# in3watch.net
KiCad netlist of a schematic drawn in EAGLE
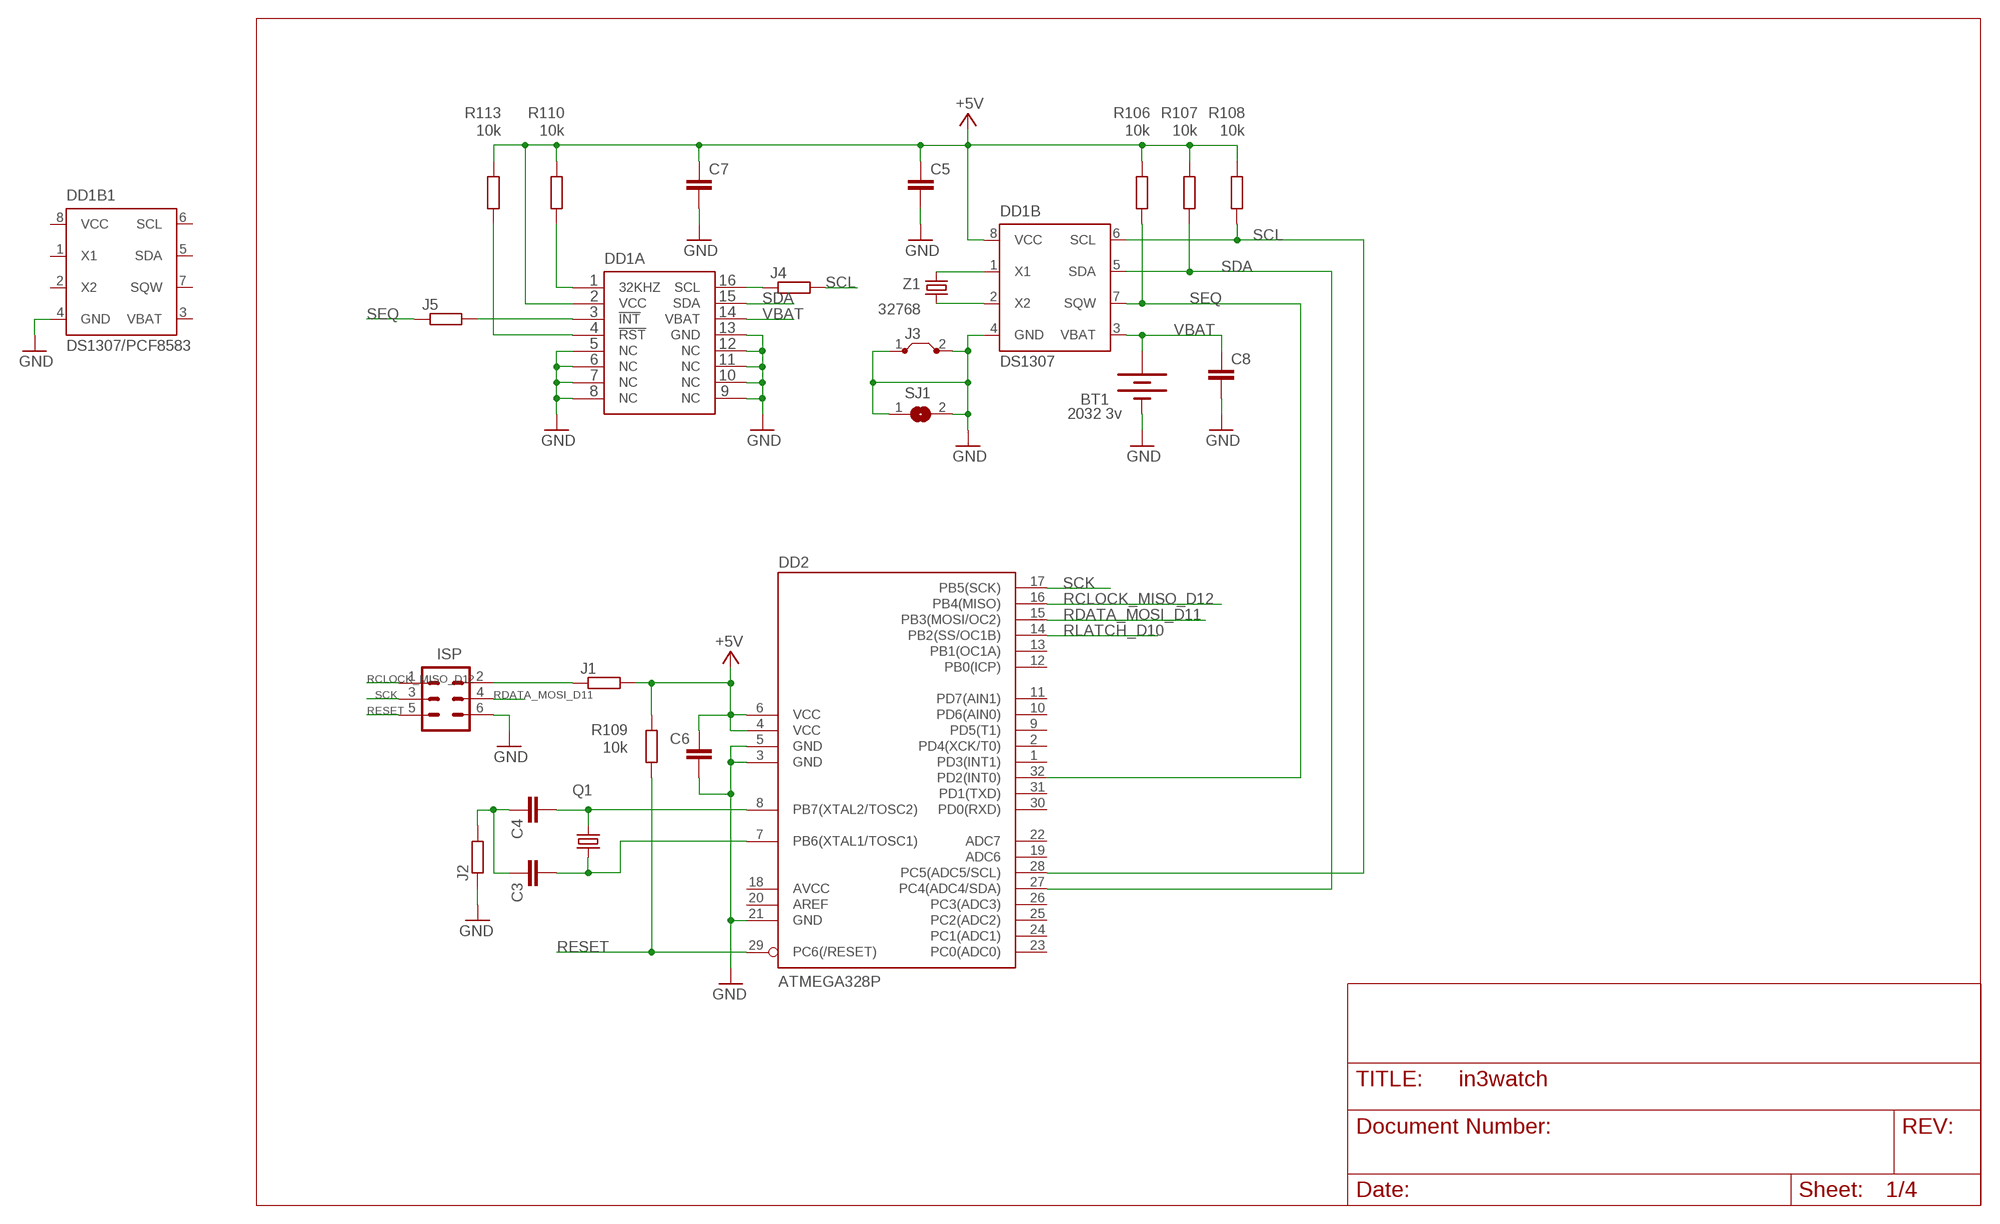
[diagram p0: schematic, sheet 1]
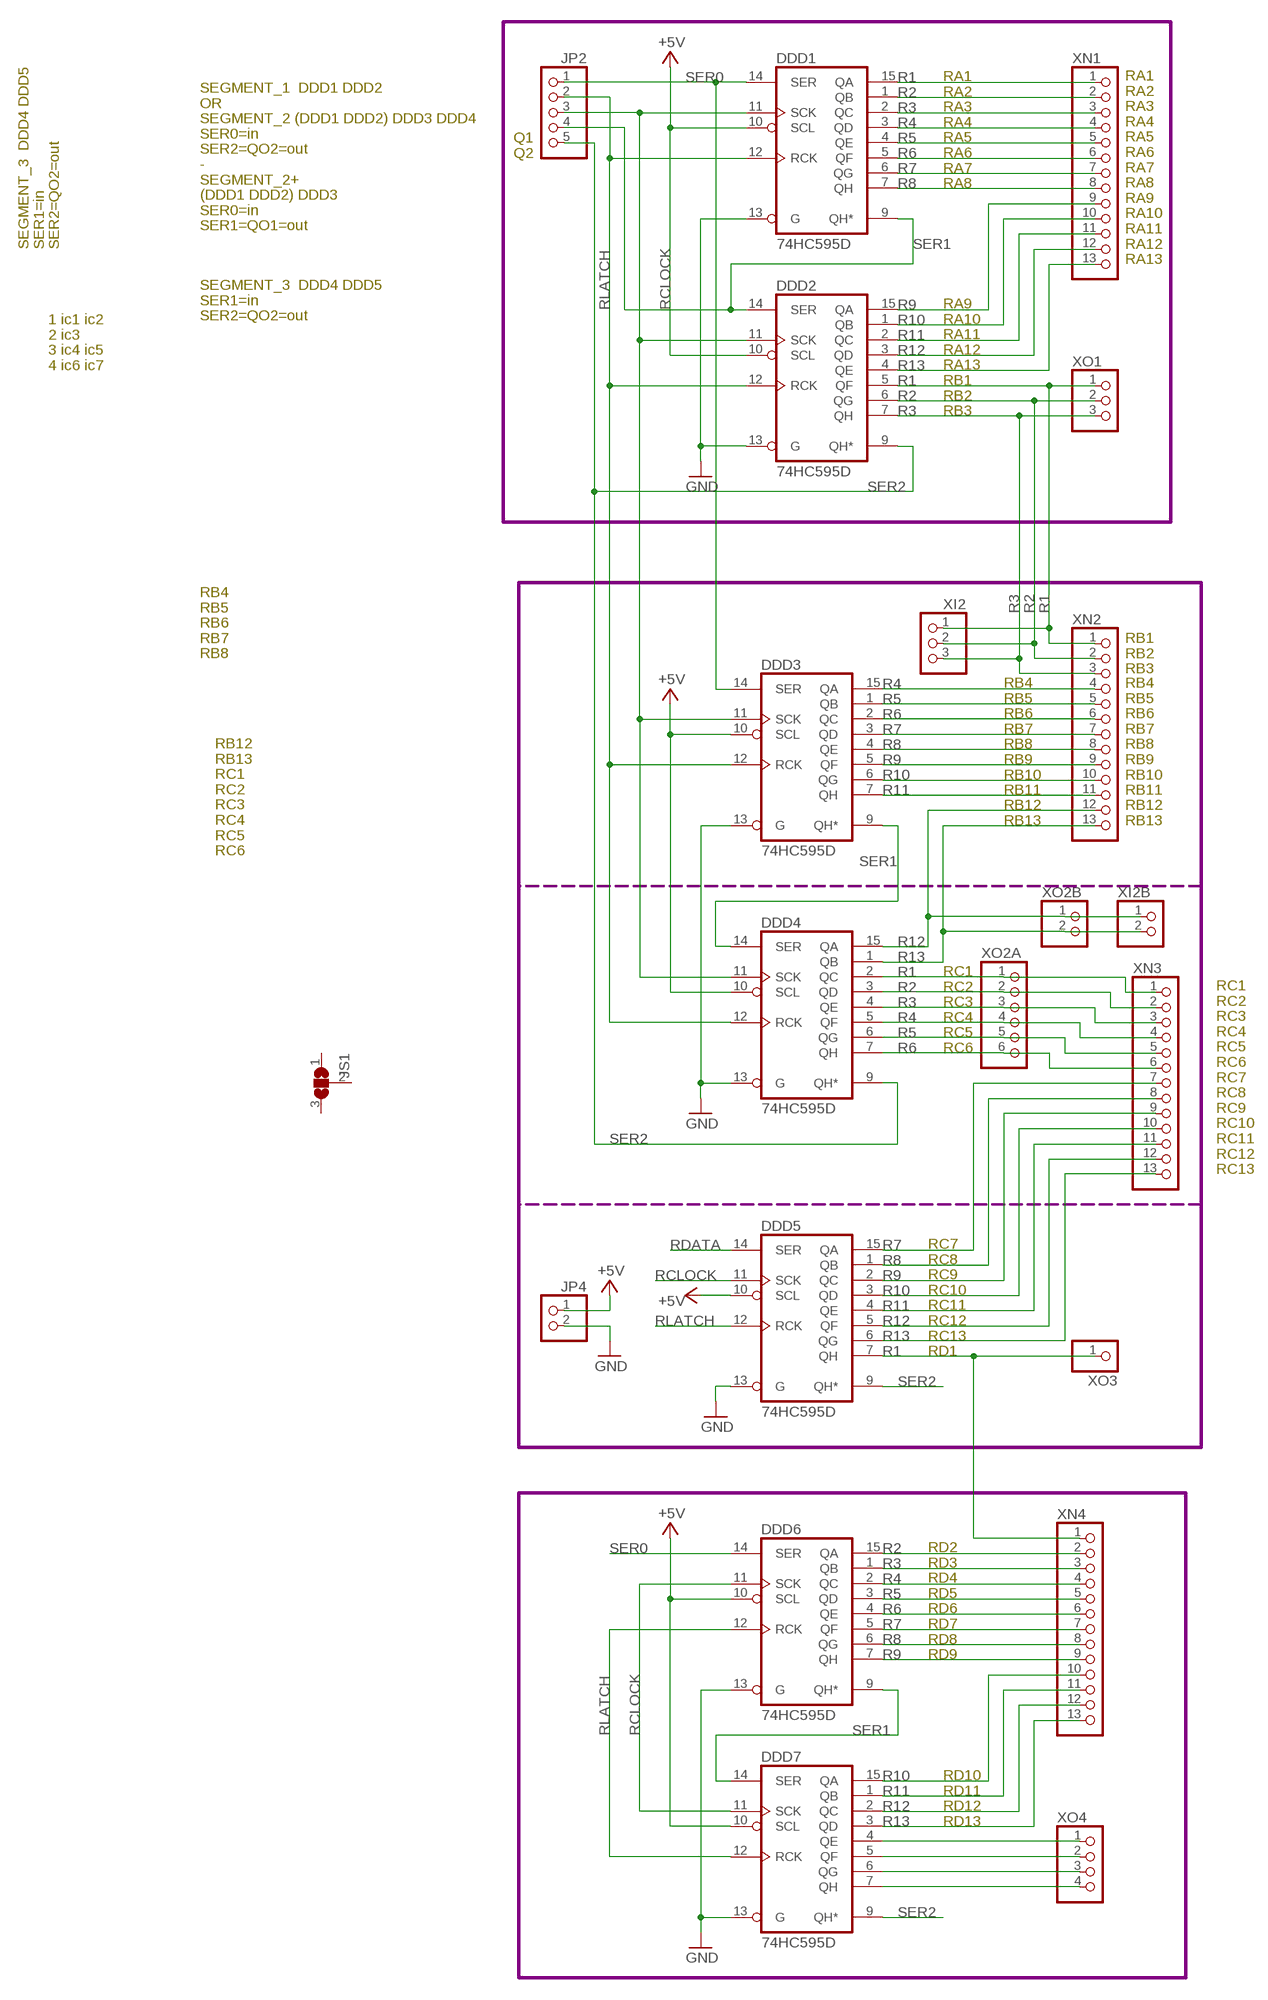
[diagram p1: schematic, sheet 2, part 1 of 2]
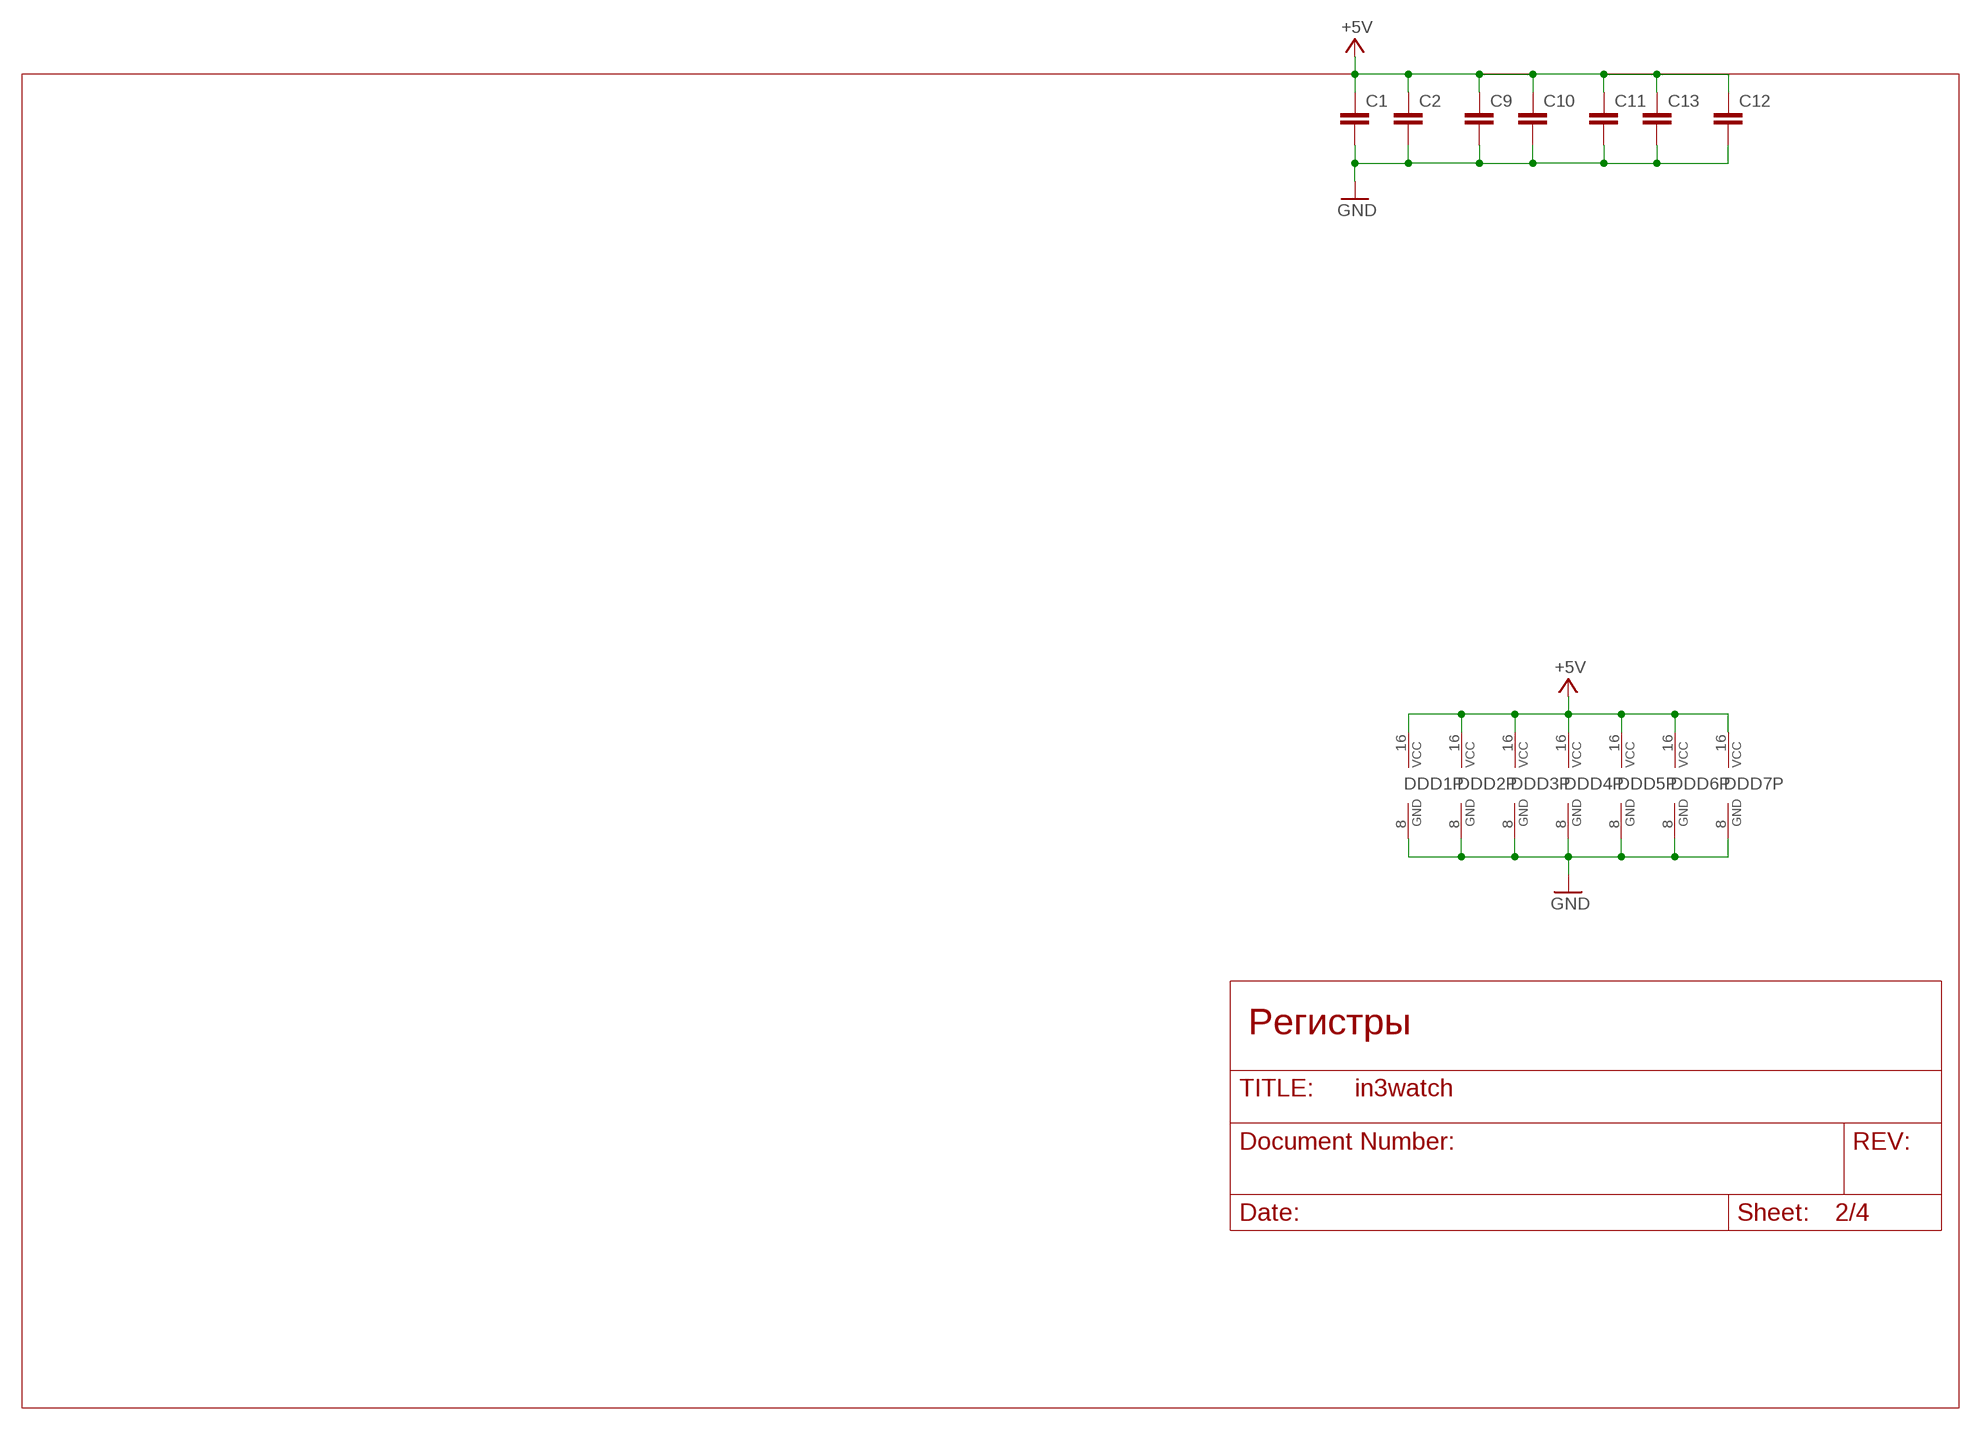
[diagram p2: schematic, sheet 2, part 2 of 2]
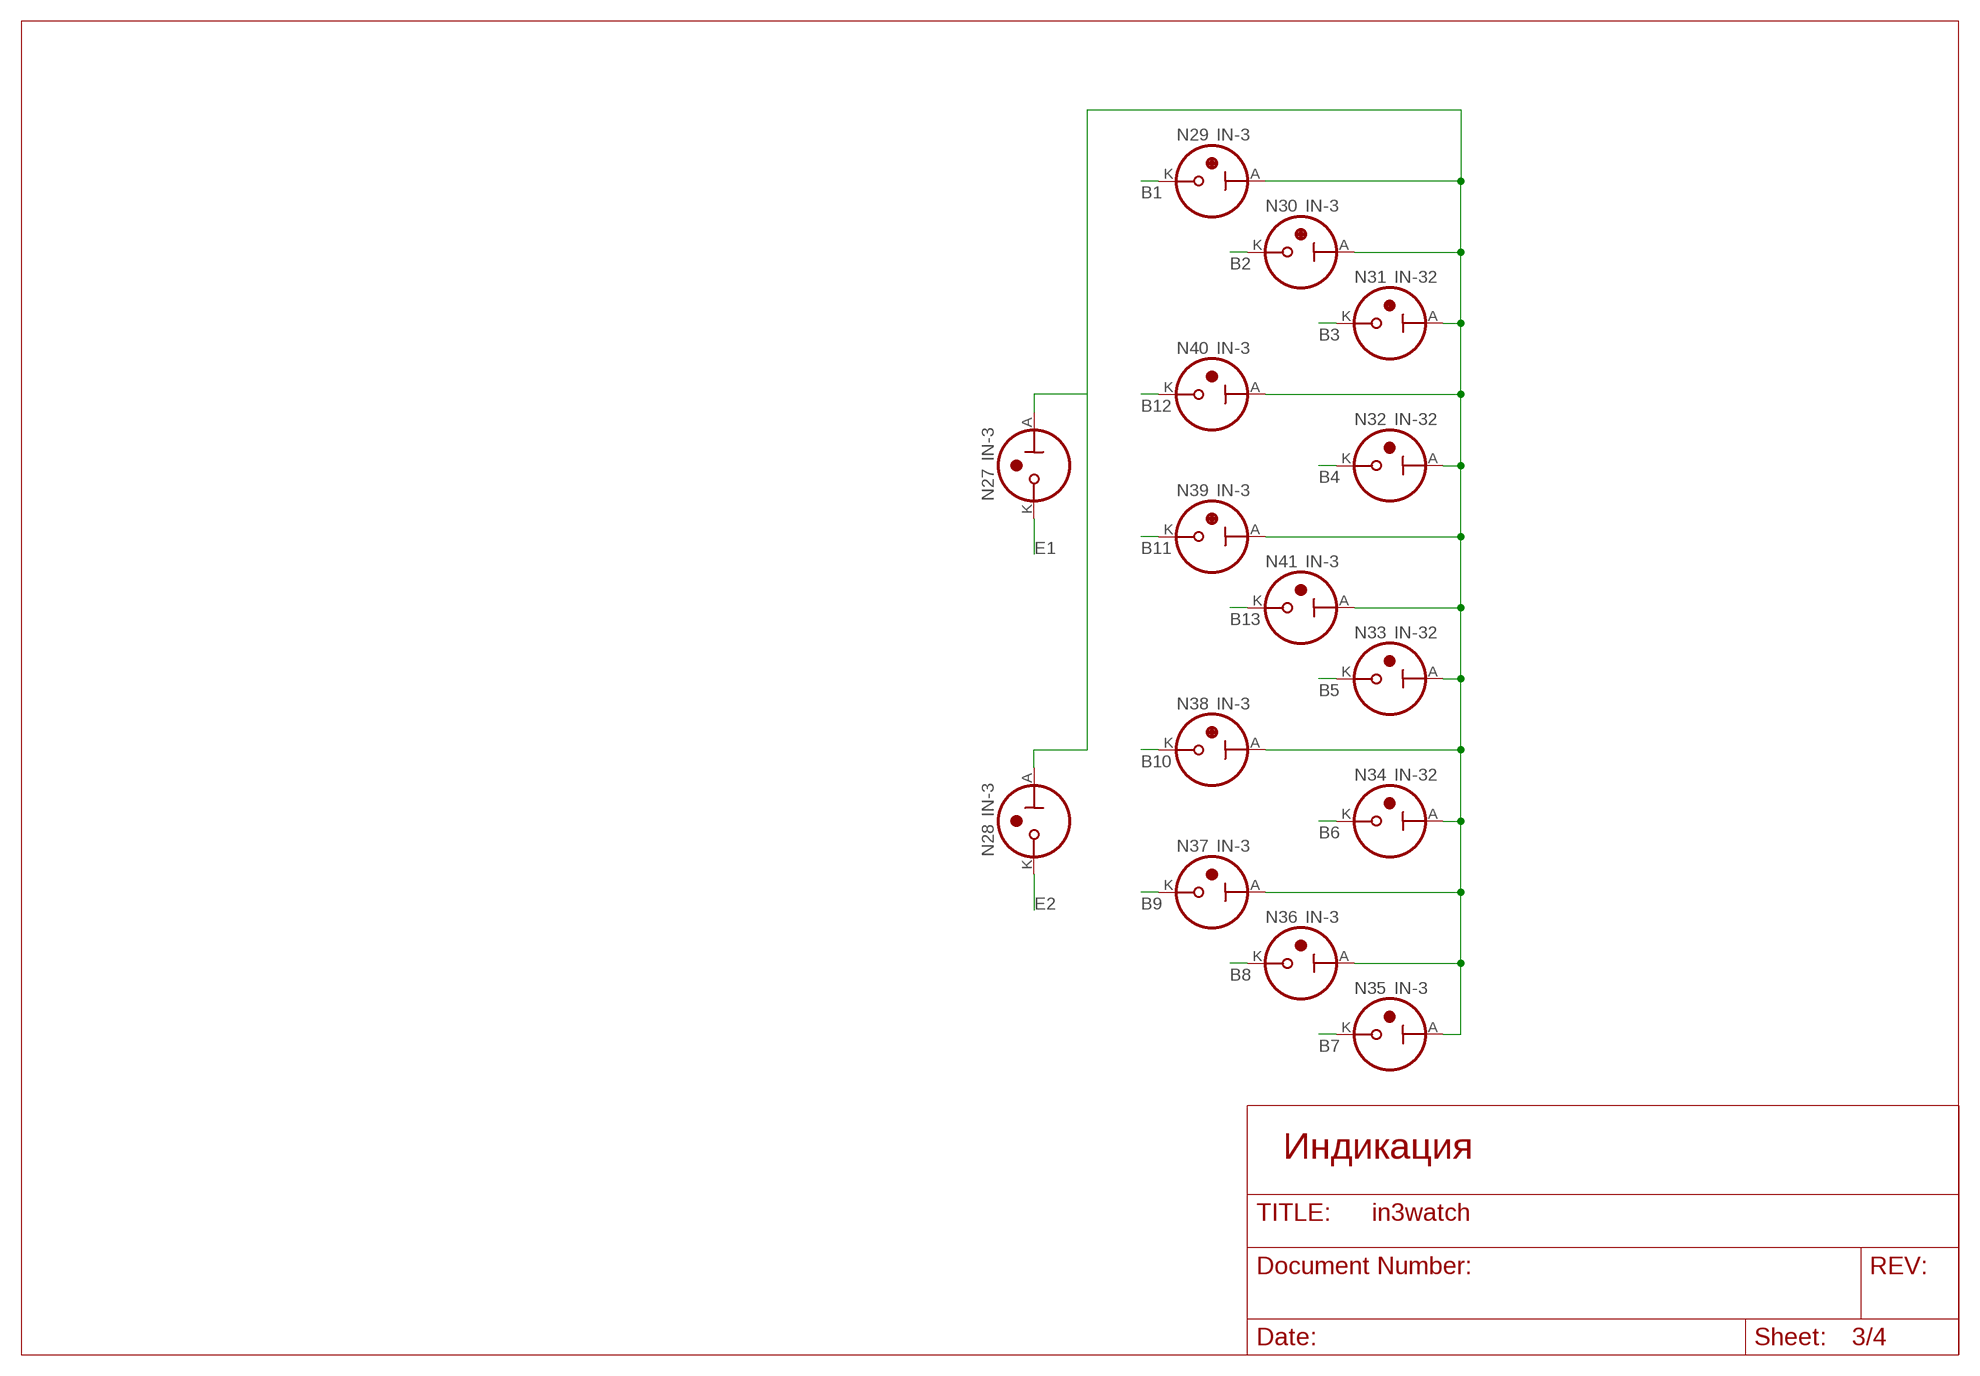
[diagram p3: schematic, sheet 3]
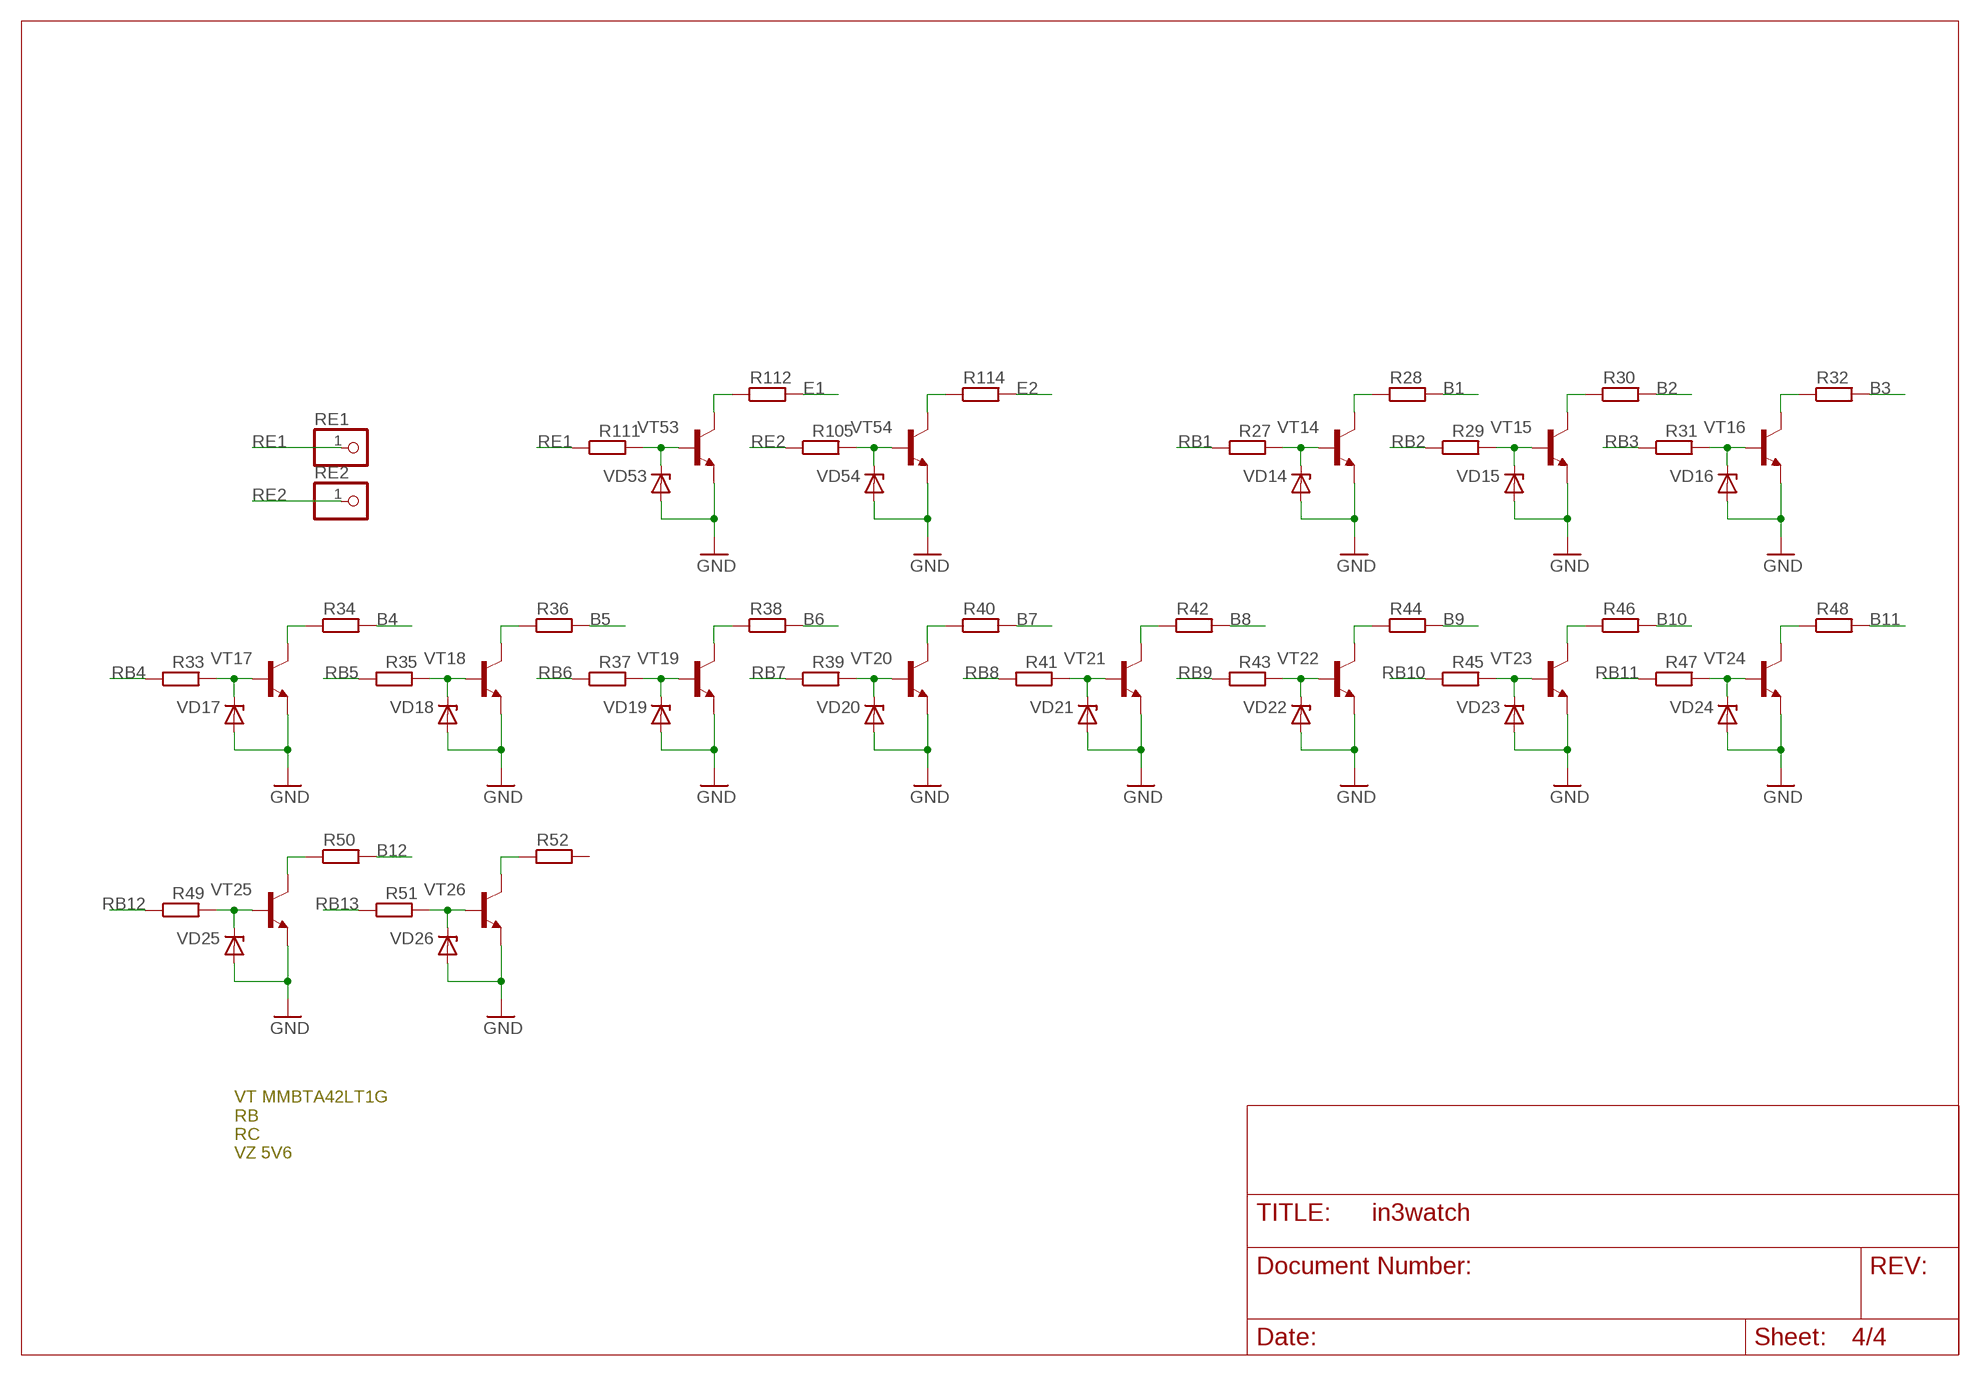
[diagram p4: schematic, sheet 4]

(export (version "E")
  (design (tool "Eeschema 10.0.6"))
  (components
    (comp (ref "C1")
      (value "C-EUC0805")
      (footprint "eagle-import:C0805")
      (libsource (lib "eagle-import") (part "C-EUC0805"))
    )
    (comp (ref "C2")
      (value "C-EUC0805")
      (footprint "eagle-import:C0805")
      (libsource (lib "eagle-import") (part "C-EUC0805"))
    )
    (comp (ref "C9")
      (value "C-EUC0805")
      (footprint "eagle-import:C0805")
      (libsource (lib "eagle-import") (part "C-EUC0805"))
    )
    (comp (ref "C10")
      (value "C-EUC0805")
      (footprint "eagle-import:C0805")
      (libsource (lib "eagle-import") (part "C-EUC0805"))
    )
    (comp (ref "C11")
      (value "C-EUC0805")
      (footprint "eagle-import:C0805")
      (libsource (lib "eagle-import") (part "C-EUC0805"))
    )
    (comp (ref "C12")
      (value "C-EUC0805")
      (footprint "eagle-import:C0805")
      (libsource (lib "eagle-import") (part "C-EUC0805"))
    )
    (comp (ref "C13")
      (value "C-EUC0805")
      (footprint "eagle-import:C0805")
      (libsource (lib "eagle-import") (part "C-EUC0805"))
    )
    (comp (ref "DDD1")
      (value "74HC595D")
      (footprint "eagle-import:SO16")
      (libsource (lib "eagle-import") (part "74595DHC"))
    )
    (comp (ref "DDD2")
      (value "74HC595D")
      (footprint "eagle-import:SO16")
      (libsource (lib "eagle-import") (part "74595DHC"))
    )
    (comp (ref "DDD3")
      (value "74HC595D")
      (footprint "eagle-import:SO16")
      (libsource (lib "eagle-import") (part "74595DHC"))
    )
    (comp (ref "DDD4")
      (value "74HC595D")
      (footprint "eagle-import:SO16")
      (libsource (lib "eagle-import") (part "74595DHC"))
    )
    (comp (ref "DDD5")
      (value "74HC595D")
      (footprint "eagle-import:SO16")
      (libsource (lib "eagle-import") (part "74595DHC"))
    )
    (comp (ref "DDD6")
      (value "74HC595D")
      (footprint "eagle-import:SO16")
      (libsource (lib "eagle-import") (part "74595DHC"))
    )
    (comp (ref "DDD7")
      (value "74HC595D")
      (footprint "eagle-import:SO16")
      (libsource (lib "eagle-import") (part "74595DHC"))
    )
    (comp (ref "JP2")
      (value "PINHD-1X5")
      (footprint "eagle-import:1X05")
      (libsource (lib "eagle-import") (part "PINHD-1X5"))
    )
    (comp (ref "JP4")
      (value "PINHD-1X2")
      (footprint "eagle-import:2X01")
      (libsource (lib "eagle-import") (part "PINHD-1X2"))
    )
    (comp (ref "JS1")
      (value "SJ2W")
      (footprint "eagle-import:SJ_2")
      (libsource (lib "eagle-import") (part "SJ2W"))
    )
    (comp (ref "XI2")
      (value "PINHD-1X3")
      (footprint "eagle-import:1X03")
      (libsource (lib "eagle-import") (part "PINHD-1X3"))
    )
    (comp (ref "XI2B")
      (value "PINHD-1X2/2")
      (footprint "eagle-import:1X02")
      (libsource (lib "eagle-import") (part "PINHD-1X2/2"))
    )
    (comp (ref "XN1")
      (value "PINHD-1X13")
      (footprint "eagle-import:1X13")
      (libsource (lib "eagle-import") (part "PINHD-1X13"))
    )
    (comp (ref "XN2")
      (value "PINHD-1X13")
      (footprint "eagle-import:1X13")
      (libsource (lib "eagle-import") (part "PINHD-1X13"))
    )
    (comp (ref "XN3")
      (value "PINHD-1X13")
      (footprint "eagle-import:1X13")
      (libsource (lib "eagle-import") (part "PINHD-1X13"))
    )
    (comp (ref "XN4")
      (value "PINHD-1X13")
      (footprint "eagle-import:1X13")
      (libsource (lib "eagle-import") (part "PINHD-1X13"))
    )
    (comp (ref "XO1")
      (value "PINHD-1X3")
      (footprint "eagle-import:1X03")
      (libsource (lib "eagle-import") (part "PINHD-1X3"))
    )
    (comp (ref "XO2A")
      (value "PINHD-1X6")
      (footprint "eagle-import:1X06")
      (libsource (lib "eagle-import") (part "PINHD-1X6"))
    )
    (comp (ref "XO2B")
      (value "PINHD-1X2/2")
      (footprint "eagle-import:1X02")
      (libsource (lib "eagle-import") (part "PINHD-1X2/2"))
    )
    (comp (ref "XO3")
      (value "PINHD-1X1")
      (footprint "eagle-import:1X01")
      (libsource (lib "eagle-import") (part "Разъёмы штырьковые 2.54мм_PINHD-1X1"))
    )
    (comp (ref "XO4")
      (value "PINHD-1X4")
      (footprint "eagle-import:1X04")
      (libsource (lib "eagle-import") (part "PINHD-1X4"))
    )
    (comp (ref "BT1")
      (value "2032 3v")
      (footprint "eagle-import:BATTCOM_20MM_PTH")
      (libsource (lib "eagle-import") (part "BATTERY-20MM_PTH"))
    )
    (comp (ref "C3")
      (value "C-EUC0805")
      (footprint "eagle-import:C0805")
      (libsource (lib "eagle-import") (part "C-EUC0805"))
    )
    (comp (ref "C4")
      (value "C-EUC0805")
      (footprint "eagle-import:C0805")
      (libsource (lib "eagle-import") (part "C-EUC0805"))
    )
    (comp (ref "C5")
      (value "C-EUC0805")
      (footprint "eagle-import:C0805")
      (libsource (lib "eagle-import") (part "C-EUC0805"))
    )
    (comp (ref "C6")
      (value "C-EUC0805")
      (footprint "eagle-import:C0805")
      (libsource (lib "eagle-import") (part "C-EUC0805"))
    )
    (comp (ref "C7")
      (value "C-EUC0805")
      (footprint "eagle-import:C0805")
      (libsource (lib "eagle-import") (part "C-EUC0805"))
    )
    (comp (ref "C8")
      (value "C-EUC3225")
      (footprint "eagle-import:C3225")
      (libsource (lib "eagle-import") (part "C-EUC3225"))
    )
    (comp (ref "DD1A")
      (value "DS3231SOIC-16W")
      (footprint "eagle-import:SOIC-16W")
      (libsource (lib "eagle-import") (part "DS3231SOIC-16W"))
    )
    (comp (ref "DD1B")
      (value "DS1307")
      (footprint "eagle-import:DIL08")
      (libsource (lib "eagle-import") (part "DS1307"))
    )
    (comp (ref "DD1B1")
      (value "DS1307/PCF8583")
      (footprint "eagle-import:SO8-7_5+SOIC8")
      (libsource (lib "eagle-import") (part "DS1307/PCF8583"))
    )
    (comp (ref "DD2")
      (value "ATMEGA328P")
      (footprint "eagle-import:TQFP32-08")
      (fields (field (name "MPN") "ATMEGA8-16AU"))
      (libsource (lib "eagle-import") (part "MEGA8-AI"))
    )
    (comp (ref "ISP")
      (value "MA03-2")
      (footprint "eagle-import:MA03-2")
      (libsource (lib "eagle-import") (part "MA03-2"))
    )
    (comp (ref "J1")
      (value "R-EU_R1206")
      (footprint "eagle-import:R1206")
      (libsource (lib "eagle-import") (part "R-EU_R1206"))
    )
    (comp (ref "J2")
      (value "R-EU_R1206")
      (footprint "eagle-import:R1206")
      (libsource (lib "eagle-import") (part "R-EU_R1206"))
    )
    (comp (ref "J3")
      (value "J5MM")
      (footprint "eagle-import:05")
      (libsource (lib "eagle-import") (part "J5MM"))
    )
    (comp (ref "J4")
      (value "R-EU_R1206W")
      (footprint "eagle-import:R1206W")
      (libsource (lib "eagle-import") (part "R-EU_R1206W"))
    )
    (comp (ref "J5")
      (value "R-EU_R1206W")
      (footprint "eagle-import:R1206W")
      (libsource (lib "eagle-import") (part "R-EU_R1206W"))
    )
    (comp (ref "Q1")
      (value "CRYSTALHC49U70")
      (footprint "eagle-import:HC49U70")
      (fields (field (name "OC_FARNELL") "unknown"))
      (libsource (lib "eagle-import") (part "CRYSTALHC49U70"))
    )
    (comp (ref "R106")
      (value "10k")
      (footprint "eagle-import:R0805")
      (libsource (lib "eagle-import") (part "R-EU_R0805"))
    )
    (comp (ref "R107")
      (value "10k")
      (footprint "eagle-import:R0805")
      (libsource (lib "eagle-import") (part "R-EU_R0805"))
    )
    (comp (ref "R108")
      (value "10k")
      (footprint "eagle-import:R0805")
      (libsource (lib "eagle-import") (part "R-EU_R0805"))
    )
    (comp (ref "R109")
      (value "10k")
      (footprint "eagle-import:R0805")
      (libsource (lib "eagle-import") (part "R-EU_R0805"))
    )
    (comp (ref "R110")
      (value "10k")
      (footprint "eagle-import:R0805")
      (libsource (lib "eagle-import") (part "R-EU_R0805"))
    )
    (comp (ref "R113")
      (value "10k")
      (footprint "eagle-import:R0805")
      (libsource (lib "eagle-import") (part "R-EU_R0805"))
    )
    (comp (ref "SJ1") (value "SJ") (footprint "eagle-import:SJ") (libsource (lib "eagle-import") (part "SJ")))
    (comp (ref "Z1")
      (value "32768")
      (footprint "eagle-import:FC-12M")
      (libsource (lib "eagle-import") (part "FC-12M"))
    )
    (comp (ref "R27")
      (value "R-EU_R0805")
      (footprint "eagle-import:R0805")
      (libsource (lib "eagle-import") (part "R-EU_R0805"))
    )
    (comp (ref "R28")
      (value "R-EU_0207/12")
      (footprint "eagle-import:0207_12")
      (libsource (lib "eagle-import") (part "R-EU_0207/12"))
    )
    (comp (ref "R29")
      (value "R-EU_R0805")
      (footprint "eagle-import:R0805")
      (libsource (lib "eagle-import") (part "R-EU_R0805"))
    )
    (comp (ref "R30")
      (value "R-EU_0207/12")
      (footprint "eagle-import:0207_12")
      (libsource (lib "eagle-import") (part "R-EU_0207/12"))
    )
    (comp (ref "R31")
      (value "R-EU_R0805")
      (footprint "eagle-import:R0805")
      (libsource (lib "eagle-import") (part "R-EU_R0805"))
    )
    (comp (ref "R32")
      (value "R-EU_0207/12")
      (footprint "eagle-import:0207_12")
      (libsource (lib "eagle-import") (part "R-EU_0207/12"))
    )
    (comp (ref "R33")
      (value "R-EU_R0805")
      (footprint "eagle-import:R0805")
      (libsource (lib "eagle-import") (part "R-EU_R0805"))
    )
    (comp (ref "R34")
      (value "R-EU_0207/12")
      (footprint "eagle-import:0207_12")
      (libsource (lib "eagle-import") (part "R-EU_0207/12"))
    )
    (comp (ref "R35")
      (value "R-EU_M1206")
      (footprint "eagle-import:M1206")
      (libsource (lib "eagle-import") (part "R-EU_M1206"))
    )
    (comp (ref "R36")
      (value "R-EU_0207/12")
      (footprint "eagle-import:0207_12")
      (libsource (lib "eagle-import") (part "R-EU_0207/12"))
    )
    (comp (ref "R37")
      (value "R-EU_R0805")
      (footprint "eagle-import:R0805")
      (libsource (lib "eagle-import") (part "R-EU_R0805"))
    )
    (comp (ref "R38")
      (value "R-EU_0207/12")
      (footprint "eagle-import:0207_12")
      (libsource (lib "eagle-import") (part "R-EU_0207/12"))
    )
    (comp (ref "R39")
      (value "R-EU_R0805")
      (footprint "eagle-import:R0805")
      (libsource (lib "eagle-import") (part "R-EU_R0805"))
    )
    (comp (ref "R40")
      (value "R-EU_0207/12")
      (footprint "eagle-import:0207_12")
      (libsource (lib "eagle-import") (part "R-EU_0207/12"))
    )
    (comp (ref "R41")
      (value "R-EU_R1206W")
      (footprint "eagle-import:R1206W")
      (libsource (lib "eagle-import") (part "R-EU_R1206W"))
    )
    (comp (ref "R42")
      (value "R-EU_0207/12")
      (footprint "eagle-import:0207_12")
      (libsource (lib "eagle-import") (part "R-EU_0207/12"))
    )
    (comp (ref "R43")
      (value "R-EU_R1206W")
      (footprint "eagle-import:R1206W")
      (libsource (lib "eagle-import") (part "R-EU_R1206W"))
    )
    (comp (ref "R44")
      (value "R-EU_0207/12")
      (footprint "eagle-import:0207_12")
      (libsource (lib "eagle-import") (part "R-EU_0207/12"))
    )
    (comp (ref "R45")
      (value "R-EU_R1206W")
      (footprint "eagle-import:R1206W")
      (libsource (lib "eagle-import") (part "R-EU_R1206W"))
    )
    (comp (ref "R46")
      (value "R-EU_0207/12")
      (footprint "eagle-import:0207_12")
      (libsource (lib "eagle-import") (part "R-EU_0207/12"))
    )
    (comp (ref "R47")
      (value "R-EU_R0805")
      (footprint "eagle-import:R0805")
      (libsource (lib "eagle-import") (part "R-EU_R0805"))
    )
    (comp (ref "R48")
      (value "R-EU_0207/10")
      (footprint "eagle-import:0207_10")
      (libsource (lib "eagle-import") (part "R-EU_0207/10"))
    )
    (comp (ref "R49")
      (value "R-EU_R0805")
      (footprint "eagle-import:R0805")
      (libsource (lib "eagle-import") (part "R-EU_R0805"))
    )
    (comp (ref "R50")
      (value "R-EU_0207/12")
      (footprint "eagle-import:0207_12")
      (libsource (lib "eagle-import") (part "R-EU_0207/12"))
    )
    (comp (ref "R51")
      (value "R-EU_R0805")
      (footprint "eagle-import:R0805")
      (libsource (lib "eagle-import") (part "R-EU_R0805"))
    )
    (comp (ref "R52")
      (value "R-EU_0207/12")
      (footprint "eagle-import:0207_12")
      (libsource (lib "eagle-import") (part "R-EU_0207/12"))
    )
    (comp (ref "R105")
      (value "R-EU_R0805")
      (footprint "eagle-import:R0805")
      (libsource (lib "eagle-import") (part "R-EU_R0805"))
    )
    (comp (ref "R111")
      (value "R-EU_R0805")
      (footprint "eagle-import:R0805")
      (libsource (lib "eagle-import") (part "R-EU_R0805"))
    )
    (comp (ref "R112")
      (value "R-EU_M0805")
      (footprint "eagle-import:M0805")
      (libsource (lib "eagle-import") (part "R-EU_M0805"))
    )
    (comp (ref "R114")
      (value "R-EU_M0805")
      (footprint "eagle-import:M0805")
      (libsource (lib "eagle-import") (part "R-EU_M0805"))
    )
    (comp (ref "RE1")
      (value "PINHD-1X1")
      (footprint "eagle-import:1X01")
      (libsource (lib "eagle-import") (part "PINHD-1X1"))
    )
    (comp (ref "RE2")
      (value "PINHD-1X1")
      (footprint "eagle-import:1X01")
      (libsource (lib "eagle-import") (part "PINHD-1X1"))
    )
    (comp (ref "VD14")
      (value "ZENER-DIODESOD80C")
      (footprint "eagle-import:SOD80C")
      (libsource (lib "eagle-import") (part "ZENER-DIODESOD80C"))
    )
    (comp (ref "VD15")
      (value "ZENER-DIODESOD80C")
      (footprint "eagle-import:SOD80C")
      (libsource (lib "eagle-import") (part "ZENER-DIODESOD80C"))
    )
    (comp (ref "VD16")
      (value "ZENER-DIODESOD80C")
      (footprint "eagle-import:SOD80C")
      (libsource (lib "eagle-import") (part "ZENER-DIODESOD80C"))
    )
    (comp (ref "VD17")
      (value "ZENER-DIODESOD80C")
      (footprint "eagle-import:SOD80C")
      (libsource (lib "eagle-import") (part "ZENER-DIODESOD80C"))
    )
    (comp (ref "VD18")
      (value "ZENER-DIODESOD80C")
      (footprint "eagle-import:SOD80C")
      (libsource (lib "eagle-import") (part "ZENER-DIODESOD80C"))
    )
    (comp (ref "VD19")
      (value "ZENER-DIODESOD80C")
      (footprint "eagle-import:SOD80C")
      (libsource (lib "eagle-import") (part "ZENER-DIODESOD80C"))
    )
    (comp (ref "VD20")
      (value "ZENER-DIODESOD80C")
      (footprint "eagle-import:SOD80C")
      (libsource (lib "eagle-import") (part "ZENER-DIODESOD80C"))
    )
    (comp (ref "VD21")
      (value "ZENER-DIODESOD80C")
      (footprint "eagle-import:SOD80C")
      (libsource (lib "eagle-import") (part "ZENER-DIODESOD80C"))
    )
    (comp (ref "VD22")
      (value "ZENER-DIODESOD80C")
      (footprint "eagle-import:SOD80C")
      (libsource (lib "eagle-import") (part "ZENER-DIODESOD80C"))
    )
    (comp (ref "VD23")
      (value "ZENER-DIODESOD80C")
      (footprint "eagle-import:SOD80C")
      (libsource (lib "eagle-import") (part "ZENER-DIODESOD80C"))
    )
    (comp (ref "VD24")
      (value "ZENER-DIODESOD80C")
      (footprint "eagle-import:SOD80C")
      (libsource (lib "eagle-import") (part "ZENER-DIODESOD80C"))
    )
    (comp (ref "VD25")
      (value "ZENER-DIODESOD80C")
      (footprint "eagle-import:SOD80C")
      (libsource (lib "eagle-import") (part "ZENER-DIODESOD80C"))
    )
    (comp (ref "VD26")
      (value "ZENER-DIODESOD80C")
      (footprint "eagle-import:SOD80C")
      (libsource (lib "eagle-import") (part "ZENER-DIODESOD80C"))
    )
    (comp (ref "VD53")
      (value "ZENER-DIODESOD80C")
      (footprint "eagle-import:SOD80C")
      (libsource (lib "eagle-import") (part "ZENER-DIODESOD80C"))
    )
    (comp (ref "VD54")
      (value "ZENER-DIODESOD80C")
      (footprint "eagle-import:SOD80C")
      (libsource (lib "eagle-import") (part "ZENER-DIODESOD80C"))
    )
    (comp (ref "VT14")
      (value "BC849SMD")
      (footprint "eagle-import:SOT23-BEC")
      (libsource (lib "eagle-import") (part "BC849SMD"))
    )
    (comp (ref "VT15")
      (value "BC849SMD")
      (footprint "eagle-import:SOT23-BEC")
      (libsource (lib "eagle-import") (part "BC849SMD"))
    )
    (comp (ref "VT16")
      (value "BC849SMD")
      (footprint "eagle-import:SOT23-BEC")
      (libsource (lib "eagle-import") (part "BC849SMD"))
    )
    (comp (ref "VT17")
      (value "BC849SMD")
      (footprint "eagle-import:SOT23-BEC")
      (libsource (lib "eagle-import") (part "BC849SMD"))
    )
    (comp (ref "VT18")
      (value "BC849SMD")
      (footprint "eagle-import:SOT23-BEC")
      (libsource (lib "eagle-import") (part "BC849SMD"))
    )
    (comp (ref "VT19")
      (value "BC849SMD")
      (footprint "eagle-import:SOT23-BEC")
      (libsource (lib "eagle-import") (part "BC849SMD"))
    )
    (comp (ref "VT20")
      (value "BC849SMD")
      (footprint "eagle-import:SOT23-BEC")
      (libsource (lib "eagle-import") (part "BC849SMD"))
    )
    (comp (ref "VT21")
      (value "BC849SMD")
      (footprint "eagle-import:SOT23-BEC")
      (libsource (lib "eagle-import") (part "BC849SMD"))
    )
    (comp (ref "VT22")
      (value "BC849SMD")
      (footprint "eagle-import:SOT23-BEC")
      (libsource (lib "eagle-import") (part "BC849SMD"))
    )
    (comp (ref "VT23")
      (value "BC849SMD")
      (footprint "eagle-import:SOT23-BEC")
      (libsource (lib "eagle-import") (part "BC849SMD"))
    )
    (comp (ref "VT24")
      (value "BC849SMD")
      (footprint "eagle-import:SOT23-BEC")
      (libsource (lib "eagle-import") (part "BC849SMD"))
    )
    (comp (ref "VT25")
      (value "BC849SMD")
      (footprint "eagle-import:SOT23-BEC")
      (libsource (lib "eagle-import") (part "BC849SMD"))
    )
    (comp (ref "VT26")
      (value "BC849SMD")
      (footprint "eagle-import:SOT23-BEC")
      (libsource (lib "eagle-import") (part "BC849SMD"))
    )
    (comp (ref "VT53")
      (value "BC849SMD")
      (footprint "eagle-import:SOT23-BEC")
      (libsource (lib "eagle-import") (part "BC849SMD"))
    )
    (comp (ref "VT54")
      (value "BC849SMD")
      (footprint "eagle-import:SOT23-BEC")
      (libsource (lib "eagle-import") (part "BC849SMD"))
    )
    (comp (ref "N27")
      (value "IN-3")
      (footprint "eagle-import:IN-3")
      (libsource (lib "eagle-import") (part "IN-3"))
    )
    (comp (ref "N28")
      (value "IN-3")
      (footprint "eagle-import:IN-3")
      (libsource (lib "eagle-import") (part "IN-3"))
    )
    (comp (ref "N29")
      (value "IN-3")
      (footprint "eagle-import:IN-3")
      (libsource (lib "eagle-import") (part "IN-3"))
    )
    (comp (ref "N30")
      (value "IN-3")
      (footprint "eagle-import:IN-3")
      (libsource (lib "eagle-import") (part "IN-3"))
    )
    (comp (ref "N31")
      (value "IN-32")
      (footprint "eagle-import:IN-3-2")
      (libsource (lib "eagle-import") (part "IN-32"))
    )
    (comp (ref "N32")
      (value "IN-32")
      (footprint "eagle-import:IN-3-2")
      (libsource (lib "eagle-import") (part "IN-32"))
    )
    (comp (ref "N33")
      (value "IN-32")
      (footprint "eagle-import:IN-3-2")
      (libsource (lib "eagle-import") (part "IN-32"))
    )
    (comp (ref "N34")
      (value "IN-32")
      (footprint "eagle-import:IN-3-2")
      (libsource (lib "eagle-import") (part "IN-32"))
    )
    (comp (ref "N35")
      (value "IN-3")
      (footprint "eagle-import:IN-3")
      (libsource (lib "eagle-import") (part "IN-3"))
    )
    (comp (ref "N36")
      (value "IN-3")
      (footprint "eagle-import:IN-3")
      (libsource (lib "eagle-import") (part "IN-3"))
    )
    (comp (ref "N37")
      (value "IN-3")
      (footprint "eagle-import:IN-3")
      (libsource (lib "eagle-import") (part "IN-3"))
    )
    (comp (ref "N38")
      (value "IN-3")
      (footprint "eagle-import:IN-3")
      (libsource (lib "eagle-import") (part "IN-3"))
    )
    (comp (ref "N39")
      (value "IN-3")
      (footprint "eagle-import:IN-3")
      (libsource (lib "eagle-import") (part "IN-3"))
    )
    (comp (ref "N40")
      (value "IN-3")
      (footprint "eagle-import:IN-3")
      (libsource (lib "eagle-import") (part "IN-3"))
    )
    (comp (ref "N41")
      (value "IN-3")
      (footprint "eagle-import:IN-3")
      (libsource (lib "eagle-import") (part "IN-3"))
    )
  )
  (nets
    (net (code "1") (name "+5V") (class "Default")
      (node (ref "C1") (pin "1") (pinfunction "1_1") (pintype "passive"))
      (node (ref "C10") (pin "1") (pinfunction "1_1") (pintype "passive"))
      (node (ref "C11") (pin "1") (pinfunction "1_1") (pintype "passive"))
      (node (ref "C12") (pin "1") (pinfunction "1_1") (pintype "passive"))
      (node (ref "C13") (pin "1") (pinfunction "1_1") (pintype "passive"))
      (node (ref "C2") (pin "1") (pinfunction "1_1") (pintype "passive"))
      (node (ref "C5") (pin "1") (pinfunction "1_1") (pintype "passive"))
      (node (ref "C6") (pin "1") (pinfunction "1_1") (pintype "passive"))
      (node (ref "C7") (pin "1") (pinfunction "1_1") (pintype "passive"))
      (node (ref "C9") (pin "1") (pinfunction "1_1") (pintype "passive"))
      (node (ref "DD1A") (pin "2") (pinfunction "VCC_2") (pintype "bidirectional"))
      (node (ref "DD1B") (pin "8") (pinfunction "VCC_8") (pintype "power_in"))
      (node (ref "DD2") (pin "4") (pinfunction "VCC_4") (pintype "power_in"))
      (node (ref "DD2") (pin "6") (pinfunction "VCC_6") (pintype "power_in"))
      (node (ref "DDD1") (pin "10") (pinfunction "SCL_10") (pintype "input"))
      (node (ref "DDD1") (pin "16") (pinfunction "VCC_16") (pintype "power_in"))
      (node (ref "DDD2") (pin "10") (pinfunction "SCL_10") (pintype "input"))
      (node (ref "DDD2") (pin "16") (pinfunction "VCC_16") (pintype "power_in"))
      (node (ref "DDD3") (pin "10") (pinfunction "SCL_10") (pintype "input"))
      (node (ref "DDD3") (pin "16") (pinfunction "VCC_16") (pintype "power_in"))
      (node (ref "DDD4") (pin "10") (pinfunction "SCL_10") (pintype "input"))
      (node (ref "DDD4") (pin "16") (pinfunction "VCC_16") (pintype "power_in"))
      (node (ref "DDD5") (pin "10") (pinfunction "SCL_10") (pintype "input"))
      (node (ref "DDD5") (pin "16") (pinfunction "VCC_16") (pintype "power_in"))
      (node (ref "DDD6") (pin "10") (pinfunction "SCL_10") (pintype "input"))
      (node (ref "DDD6") (pin "16") (pinfunction "VCC_16") (pintype "power_in"))
      (node (ref "DDD7") (pin "10") (pinfunction "SCL_10") (pintype "input"))
      (node (ref "DDD7") (pin "16") (pinfunction "VCC_16") (pintype "power_in"))
      (node (ref "J1") (pin "2") (pinfunction "2_2") (pintype "passive"))
      (node (ref "JP4") (pin "1") (pinfunction "1_1") (pintype "passive"))
      (node (ref "R106") (pin "2") (pinfunction "2_2") (pintype "passive"))
      (node (ref "R107") (pin "2") (pinfunction "2_2") (pintype "passive"))
      (node (ref "R108") (pin "2") (pinfunction "2_2") (pintype "passive"))
      (node (ref "R109") (pin "2") (pinfunction "2_2") (pintype "passive"))
      (node (ref "R110") (pin "2") (pinfunction "2_2") (pintype "passive"))
      (node (ref "R113") (pin "2") (pinfunction "2_2") (pintype "passive"))
    )
    (net (code "2") (name "AVCC") (class "Default")
      (node (ref "DD2") (pin "18") (pinfunction "AVCC_18") (pintype "power_in"))
    )
    (net (code "3") (name "B1") (class "Default")
      (node (ref "N29") (pin "K") (pinfunction "K_K") (pintype "bidirectional"))
      (node (ref "R28") (pin "2") (pinfunction "2_2") (pintype "passive"))
    )
    (net (code "4") (name "B2") (class "Default")
      (node (ref "N30") (pin "K") (pinfunction "K_K") (pintype "bidirectional"))
      (node (ref "R30") (pin "2") (pinfunction "2_2") (pintype "passive"))
    )
    (net (code "5") (name "B3") (class "Default")
      (node (ref "N31") (pin "K") (pinfunction "K_K") (pintype "bidirectional"))
      (node (ref "R32") (pin "2") (pinfunction "2_2") (pintype "passive"))
    )
    (net (code "6") (name "B4") (class "Default")
      (node (ref "N32") (pin "K") (pinfunction "K_K") (pintype "bidirectional"))
      (node (ref "R34") (pin "2") (pinfunction "2_2") (pintype "passive"))
    )
    (net (code "7") (name "B5") (class "Default")
      (node (ref "N33") (pin "K") (pinfunction "K_K") (pintype "bidirectional"))
      (node (ref "R36") (pin "2") (pinfunction "2_2") (pintype "passive"))
    )
    (net (code "8") (name "B6") (class "Default")
      (node (ref "N34") (pin "K") (pinfunction "K_K") (pintype "bidirectional"))
      (node (ref "R38") (pin "2") (pinfunction "2_2") (pintype "passive"))
    )
    (net (code "9") (name "B7") (class "Default")
      (node (ref "N35") (pin "K") (pinfunction "K_K") (pintype "bidirectional"))
      (node (ref "R40") (pin "2") (pinfunction "2_2") (pintype "passive"))
    )
    (net (code "10") (name "B8") (class "Default")
      (node (ref "N36") (pin "K") (pinfunction "K_K") (pintype "bidirectional"))
      (node (ref "R42") (pin "2") (pinfunction "2_2") (pintype "passive"))
    )
    (net (code "11") (name "B9") (class "Default")
      (node (ref "N37") (pin "K") (pinfunction "K_K") (pintype "bidirectional"))
      (node (ref "R44") (pin "2") (pinfunction "2_2") (pintype "passive"))
    )
    (net (code "12") (name "B10") (class "Default")
      (node (ref "N38") (pin "K") (pinfunction "K_K") (pintype "bidirectional"))
      (node (ref "R46") (pin "2") (pinfunction "2_2") (pintype "passive"))
    )
    (net (code "13") (name "B11") (class "Default")
      (node (ref "N39") (pin "K") (pinfunction "K_K") (pintype "bidirectional"))
      (node (ref "R48") (pin "2") (pinfunction "2_2") (pintype "passive"))
    )
    (net (code "14") (name "B12") (class "Default")
      (node (ref "N40") (pin "K") (pinfunction "K_K") (pintype "bidirectional"))
      (node (ref "R50") (pin "2") (pinfunction "2_2") (pintype "passive"))
    )
    (net (code "15") (name "B13") (class "Default")
      (node (ref "N41") (pin "K") (pinfunction "K_K") (pintype "bidirectional"))
    )
    (net (code "16") (name "E1") (class "Default")
      (node (ref "N27") (pin "K") (pinfunction "K_K") (pintype "bidirectional"))
      (node (ref "R112") (pin "2") (pinfunction "2_2") (pintype "passive"))
    )
    (net (code "17") (name "E2") (class "Default")
      (node (ref "N28") (pin "K") (pinfunction "K_K") (pintype "bidirectional"))
      (node (ref "R114") (pin "2") (pinfunction "2_2") (pintype "passive"))
    )
    (net (code "18") (name "GND") (class "Default")
      (node (ref "BT1") (pin "2") (pinfunction "-_2") (pintype "power_in"))
      (node (ref "C1") (pin "2") (pinfunction "2_2") (pintype "passive"))
      (node (ref "C10") (pin "2") (pinfunction "2_2") (pintype "passive"))
      (node (ref "C11") (pin "2") (pinfunction "2_2") (pintype "passive"))
      (node (ref "C12") (pin "2") (pinfunction "2_2") (pintype "passive"))
      (node (ref "C13") (pin "2") (pinfunction "2_2") (pintype "passive"))
      (node (ref "C2") (pin "2") (pinfunction "2_2") (pintype "passive"))
      (node (ref "C5") (pin "2") (pinfunction "2_2") (pintype "passive"))
      (node (ref "C6") (pin "2") (pinfunction "2_2") (pintype "passive"))
      (node (ref "C7") (pin "2") (pinfunction "2_2") (pintype "passive"))
      (node (ref "C8") (pin "2") (pinfunction "2_2") (pintype "passive"))
      (node (ref "C9") (pin "2") (pinfunction "2_2") (pintype "passive"))
      (node (ref "DD1A") (pin "10") (pinfunction "NC_10") (pintype "bidirectional"))
      (node (ref "DD1A") (pin "11") (pinfunction "NC_11") (pintype "bidirectional"))
      (node (ref "DD1A") (pin "12") (pinfunction "NC_12") (pintype "bidirectional"))
      (node (ref "DD1A") (pin "13") (pinfunction "GND_13") (pintype "bidirectional"))
      (node (ref "DD1A") (pin "5") (pinfunction "NC_5") (pintype "bidirectional"))
      (node (ref "DD1A") (pin "6") (pinfunction "NC_6") (pintype "bidirectional"))
      (node (ref "DD1A") (pin "7") (pinfunction "NC_7") (pintype "bidirectional"))
      (node (ref "DD1A") (pin "8") (pinfunction "NC_8") (pintype "bidirectional"))
      (node (ref "DD1A") (pin "9") (pinfunction "NC_9") (pintype "bidirectional"))
      (node (ref "DD1B") (pin "4") (pinfunction "GND_4") (pintype "power_in"))
      (node (ref "DD1B1") (pin "4") (pinfunction "GND_4") (pintype "power_in"))
      (node (ref "DD2") (pin "21") (pinfunction "GND_21") (pintype "power_in"))
      (node (ref "DD2") (pin "3") (pinfunction "GND_3") (pintype "power_in"))
      (node (ref "DD2") (pin "5") (pinfunction "GND_5") (pintype "power_in"))
      (node (ref "DDD1") (pin "13") (pinfunction "G_13") (pintype "input"))
      (node (ref "DDD1") (pin "8") (pinfunction "GND_8") (pintype "power_in"))
      (node (ref "DDD2") (pin "13") (pinfunction "G_13") (pintype "input"))
      (node (ref "DDD2") (pin "8") (pinfunction "GND_8") (pintype "power_in"))
      (node (ref "DDD3") (pin "13") (pinfunction "G_13") (pintype "input"))
      (node (ref "DDD3") (pin "8") (pinfunction "GND_8") (pintype "power_in"))
      (node (ref "DDD4") (pin "13") (pinfunction "G_13") (pintype "input"))
      (node (ref "DDD4") (pin "8") (pinfunction "GND_8") (pintype "power_in"))
      (node (ref "DDD5") (pin "13") (pinfunction "G_13") (pintype "input"))
      (node (ref "DDD5") (pin "8") (pinfunction "GND_8") (pintype "power_in"))
      (node (ref "DDD6") (pin "13") (pinfunction "G_13") (pintype "input"))
      (node (ref "DDD6") (pin "8") (pinfunction "GND_8") (pintype "power_in"))
      (node (ref "DDD7") (pin "13") (pinfunction "G_13") (pintype "input"))
      (node (ref "DDD7") (pin "8") (pinfunction "GND_8") (pintype "power_in"))
      (node (ref "ISP") (pin "6") (pinfunction "6_6") (pintype "passive"))
      (node (ref "J2") (pin "1") (pinfunction "1_1") (pintype "passive"))
      (node (ref "J3") (pin "1") (pinfunction "1_1") (pintype "passive"))
      (node (ref "J3") (pin "2") (pinfunction "2_2") (pintype "passive"))
      (node (ref "JP4") (pin "2") (pinfunction "2_2") (pintype "passive"))
      (node (ref "SJ1") (pin "1") (pinfunction "1_1") (pintype "passive"))
      (node (ref "SJ1") (pin "2") (pinfunction "2_2") (pintype "passive"))
      (node (ref "VD14") (pin "A") (pinfunction "A_A") (pintype "passive"))
      (node (ref "VD15") (pin "A") (pinfunction "A_A") (pintype "passive"))
      (node (ref "VD16") (pin "A") (pinfunction "A_A") (pintype "passive"))
      (node (ref "VD17") (pin "A") (pinfunction "A_A") (pintype "passive"))
      (node (ref "VD18") (pin "A") (pinfunction "A_A") (pintype "passive"))
      (node (ref "VD19") (pin "A") (pinfunction "A_A") (pintype "passive"))
      (node (ref "VD20") (pin "A") (pinfunction "A_A") (pintype "passive"))
      (node (ref "VD21") (pin "A") (pinfunction "A_A") (pintype "passive"))
      (node (ref "VD22") (pin "A") (pinfunction "A_A") (pintype "passive"))
      (node (ref "VD23") (pin "A") (pinfunction "A_A") (pintype "passive"))
      (node (ref "VD24") (pin "A") (pinfunction "A_A") (pintype "passive"))
      (node (ref "VD25") (pin "A") (pinfunction "A_A") (pintype "passive"))
      (node (ref "VD26") (pin "A") (pinfunction "A_A") (pintype "passive"))
      (node (ref "VD53") (pin "A") (pinfunction "A_A") (pintype "passive"))
      (node (ref "VD54") (pin "A") (pinfunction "A_A") (pintype "passive"))
      (node (ref "VT14") (pin "E") (pinfunction "E_E") (pintype "passive"))
      (node (ref "VT15") (pin "E") (pinfunction "E_E") (pintype "passive"))
      (node (ref "VT16") (pin "E") (pinfunction "E_E") (pintype "passive"))
      (node (ref "VT17") (pin "E") (pinfunction "E_E") (pintype "passive"))
      (node (ref "VT18") (pin "E") (pinfunction "E_E") (pintype "passive"))
      (node (ref "VT19") (pin "E") (pinfunction "E_E") (pintype "passive"))
      (node (ref "VT20") (pin "E") (pinfunction "E_E") (pintype "passive"))
      (node (ref "VT21") (pin "E") (pinfunction "E_E") (pintype "passive"))
      (node (ref "VT22") (pin "E") (pinfunction "E_E") (pintype "passive"))
      (node (ref "VT23") (pin "E") (pinfunction "E_E") (pintype "passive"))
      (node (ref "VT24") (pin "E") (pinfunction "E_E") (pintype "passive"))
      (node (ref "VT25") (pin "E") (pinfunction "E_E") (pintype "passive"))
      (node (ref "VT26") (pin "E") (pinfunction "E_E") (pintype "passive"))
      (node (ref "VT53") (pin "E") (pinfunction "E_E") (pintype "passive"))
      (node (ref "VT54") (pin "E") (pinfunction "E_E") (pintype "passive"))
    )
    (net (code "19") (name "Net-(C3-Pad1)") (class "Default")
      (node (ref "C3") (pin "1") (pinfunction "1_1") (pintype "passive"))
      (node (ref "C4") (pin "1") (pinfunction "1_1") (pintype "passive"))
      (node (ref "J2") (pin "2") (pinfunction "2_2") (pintype "passive"))
    )
    (net (code "20") (name "Net-(DD1A-32KHZ)") (class "Default")
      (node (ref "DD1A") (pin "1") (pinfunction "32KHZ_1") (pintype "bidirectional"))
      (node (ref "R110") (pin "1") (pinfunction "1_1") (pintype "passive"))
    )
    (net (code "21") (name "Net-(DD1A-SCL)") (class "Default")
      (node (ref "DD1A") (pin "16") (pinfunction "SCL_16") (pintype "bidirectional"))
      (node (ref "J4") (pin "1") (pinfunction "1_1") (pintype "passive"))
    )
    (net (code "22") (name "Net-(DD1A-~{INT})") (class "Default")
      (node (ref "DD1A") (pin "3") (pinfunction "~{INT}_3") (pintype "bidirectional"))
      (node (ref "J5") (pin "2") (pinfunction "2_2") (pintype "passive"))
    )
    (net (code "23") (name "Net-(DD1A-~{RST})") (class "Default")
      (node (ref "DD1A") (pin "4") (pinfunction "~{RST}_4") (pintype "bidirectional"))
      (node (ref "R113") (pin "1") (pinfunction "1_1") (pintype "passive"))
    )
    (net (code "24") (name "Net-(DD1B-X1)") (class "Default")
      (node (ref "DD1B") (pin "1") (pinfunction "X1_1") (pintype "input"))
      (node (ref "Z1") (pin "P$2") (pinfunction "2_P$2") (pintype "passive"))
    )
    (net (code "25") (name "Net-(DD1B-X2)") (class "Default")
      (node (ref "DD1B") (pin "2") (pinfunction "X2_2") (pintype "output"))
      (node (ref "Z1") (pin "P$1") (pinfunction "1_P$1") (pintype "passive"))
    )
    (net (code "26") (name "Net-(DD2-PB6(XTAL1{slash}TOSC1))") (class "Default")
      (node (ref "C3") (pin "2") (pinfunction "2_2") (pintype "passive"))
      (node (ref "DD2") (pin "7") (pinfunction "PB6(XTAL1/TOSC1)_7") (pintype "bidirectional"))
      (node (ref "Q1") (pin "2") (pinfunction "2_2") (pintype "passive"))
    )
    (net (code "27") (name "Net-(DD2-PB7(XTAL2{slash}TOSC2))") (class "Default")
      (node (ref "C4") (pin "2") (pinfunction "2_2") (pintype "passive"))
      (node (ref "DD2") (pin "8") (pinfunction "PB7(XTAL2/TOSC2)_8") (pintype "bidirectional"))
      (node (ref "Q1") (pin "1") (pinfunction "1_1") (pintype "passive"))
    )
    (net (code "28") (name "Net-(DDD7A-QE)") (class "Default")
      (node (ref "DDD7") (pin "4") (pinfunction "QE_4") (pintype "tri_state"))
      (node (ref "XO4") (pin "1") (pinfunction "1_1") (pintype "passive"))
    )
    (net (code "29") (name "Net-(DDD7A-QF)") (class "Default")
      (node (ref "DDD7") (pin "5") (pinfunction "QF_5") (pintype "tri_state"))
      (node (ref "XO4") (pin "2") (pinfunction "2_2") (pintype "passive"))
    )
    (net (code "30") (name "Net-(DDD7A-QG)") (class "Default")
      (node (ref "DDD7") (pin "6") (pinfunction "QG_6") (pintype "tri_state"))
      (node (ref "XO4") (pin "3") (pinfunction "3_3") (pintype "passive"))
    )
    (net (code "31") (name "Net-(DDD7A-QH)") (class "Default")
      (node (ref "DDD7") (pin "7") (pinfunction "QH_7") (pintype "tri_state"))
      (node (ref "XO4") (pin "4") (pinfunction "4_4") (pintype "passive"))
    )
    (net (code "32") (name "Net-(ISP-Pad2)") (class "Default")
      (node (ref "ISP") (pin "2") (pinfunction "2_2") (pintype "passive"))
      (node (ref "J1") (pin "1") (pinfunction "1_1") (pintype "passive"))
    )
    (net (code "33") (name "Net-(N27-PadA)") (class "Default")
      (node (ref "N27") (pin "A") (pinfunction "A_A") (pintype "bidirectional"))
      (node (ref "N28") (pin "A") (pinfunction "A_A") (pintype "bidirectional"))
      (node (ref "N29") (pin "A") (pinfunction "A_A") (pintype "bidirectional"))
      (node (ref "N30") (pin "A") (pinfunction "A_A") (pintype "bidirectional"))
      (node (ref "N31") (pin "A") (pinfunction "A_A") (pintype "bidirectional"))
      (node (ref "N32") (pin "A") (pinfunction "A_A") (pintype "bidirectional"))
      (node (ref "N33") (pin "A") (pinfunction "A_A") (pintype "bidirectional"))
      (node (ref "N34") (pin "A") (pinfunction "A_A") (pintype "bidirectional"))
      (node (ref "N35") (pin "A") (pinfunction "A_A") (pintype "bidirectional"))
      (node (ref "N36") (pin "A") (pinfunction "A_A") (pintype "bidirectional"))
      (node (ref "N37") (pin "A") (pinfunction "A_A") (pintype "bidirectional"))
      (node (ref "N38") (pin "A") (pinfunction "A_A") (pintype "bidirectional"))
      (node (ref "N39") (pin "A") (pinfunction "A_A") (pintype "bidirectional"))
      (node (ref "N40") (pin "A") (pinfunction "A_A") (pintype "bidirectional"))
      (node (ref "N41") (pin "A") (pinfunction "A_A") (pintype "bidirectional"))
    )
    (net (code "34") (name "Net-(R27-Pad2)") (class "Default")
      (node (ref "R27") (pin "2") (pinfunction "2_2") (pintype "passive"))
      (node (ref "VD14") (pin "C") (pinfunction "C_C") (pintype "passive"))
      (node (ref "VT14") (pin "B") (pinfunction "B_B") (pintype "passive"))
    )
    (net (code "35") (name "Net-(R28-Pad1)") (class "Default")
      (node (ref "R28") (pin "1") (pinfunction "1_1") (pintype "passive"))
      (node (ref "VT14") (pin "C") (pinfunction "C_C") (pintype "passive"))
    )
    (net (code "36") (name "Net-(R29-Pad2)") (class "Default")
      (node (ref "R29") (pin "2") (pinfunction "2_2") (pintype "passive"))
      (node (ref "VD15") (pin "C") (pinfunction "C_C") (pintype "passive"))
      (node (ref "VT15") (pin "B") (pinfunction "B_B") (pintype "passive"))
    )
    (net (code "37") (name "Net-(R30-Pad1)") (class "Default")
      (node (ref "R30") (pin "1") (pinfunction "1_1") (pintype "passive"))
      (node (ref "VT15") (pin "C") (pinfunction "C_C") (pintype "passive"))
    )
    (net (code "38") (name "Net-(R31-Pad2)") (class "Default")
      (node (ref "R31") (pin "2") (pinfunction "2_2") (pintype "passive"))
      (node (ref "VD16") (pin "C") (pinfunction "C_C") (pintype "passive"))
      (node (ref "VT16") (pin "B") (pinfunction "B_B") (pintype "passive"))
    )
    (net (code "39") (name "Net-(R32-Pad1)") (class "Default")
      (node (ref "R32") (pin "1") (pinfunction "1_1") (pintype "passive"))
      (node (ref "VT16") (pin "C") (pinfunction "C_C") (pintype "passive"))
    )
    (net (code "40") (name "Net-(R33-Pad2)") (class "Default")
      (node (ref "R33") (pin "2") (pinfunction "2_2") (pintype "passive"))
      (node (ref "VD17") (pin "C") (pinfunction "C_C") (pintype "passive"))
      (node (ref "VT17") (pin "B") (pinfunction "B_B") (pintype "passive"))
    )
    (net (code "41") (name "Net-(R34-Pad1)") (class "Default")
      (node (ref "R34") (pin "1") (pinfunction "1_1") (pintype "passive"))
      (node (ref "VT17") (pin "C") (pinfunction "C_C") (pintype "passive"))
    )
    (net (code "42") (name "Net-(R35-Pad2)") (class "Default")
      (node (ref "R35") (pin "2") (pinfunction "2_2") (pintype "passive"))
      (node (ref "VD18") (pin "C") (pinfunction "C_C") (pintype "passive"))
      (node (ref "VT18") (pin "B") (pinfunction "B_B") (pintype "passive"))
    )
    (net (code "43") (name "Net-(R36-Pad1)") (class "Default")
      (node (ref "R36") (pin "1") (pinfunction "1_1") (pintype "passive"))
      (node (ref "VT18") (pin "C") (pinfunction "C_C") (pintype "passive"))
    )
    (net (code "44") (name "Net-(R37-Pad2)") (class "Default")
      (node (ref "R37") (pin "2") (pinfunction "2_2") (pintype "passive"))
      (node (ref "VD19") (pin "C") (pinfunction "C_C") (pintype "passive"))
      (node (ref "VT19") (pin "B") (pinfunction "B_B") (pintype "passive"))
    )
    (net (code "45") (name "Net-(R38-Pad1)") (class "Default")
      (node (ref "R38") (pin "1") (pinfunction "1_1") (pintype "passive"))
      (node (ref "VT19") (pin "C") (pinfunction "C_C") (pintype "passive"))
    )
    (net (code "46") (name "Net-(R39-Pad2)") (class "Default")
      (node (ref "R39") (pin "2") (pinfunction "2_2") (pintype "passive"))
      (node (ref "VD20") (pin "C") (pinfunction "C_C") (pintype "passive"))
      (node (ref "VT20") (pin "B") (pinfunction "B_B") (pintype "passive"))
    )
    (net (code "47") (name "Net-(R40-Pad1)") (class "Default")
      (node (ref "R40") (pin "1") (pinfunction "1_1") (pintype "passive"))
      (node (ref "VT20") (pin "C") (pinfunction "C_C") (pintype "passive"))
    )
    (net (code "48") (name "Net-(R41-Pad2)") (class "Default")
      (node (ref "R41") (pin "2") (pinfunction "2_2") (pintype "passive"))
      (node (ref "VD21") (pin "C") (pinfunction "C_C") (pintype "passive"))
      (node (ref "VT21") (pin "B") (pinfunction "B_B") (pintype "passive"))
    )
    (net (code "49") (name "Net-(R42-Pad1)") (class "Default")
      (node (ref "R42") (pin "1") (pinfunction "1_1") (pintype "passive"))
      (node (ref "VT21") (pin "C") (pinfunction "C_C") (pintype "passive"))
    )
    (net (code "50") (name "Net-(R43-Pad2)") (class "Default")
      (node (ref "R43") (pin "2") (pinfunction "2_2") (pintype "passive"))
      (node (ref "VD22") (pin "C") (pinfunction "C_C") (pintype "passive"))
      (node (ref "VT22") (pin "B") (pinfunction "B_B") (pintype "passive"))
    )
    (net (code "51") (name "Net-(R44-Pad1)") (class "Default")
      (node (ref "R44") (pin "1") (pinfunction "1_1") (pintype "passive"))
      (node (ref "VT22") (pin "C") (pinfunction "C_C") (pintype "passive"))
    )
    (net (code "52") (name "Net-(R45-Pad2)") (class "Default")
      (node (ref "R45") (pin "2") (pinfunction "2_2") (pintype "passive"))
      (node (ref "VD23") (pin "C") (pinfunction "C_C") (pintype "passive"))
      (node (ref "VT23") (pin "B") (pinfunction "B_B") (pintype "passive"))
    )
    (net (code "53") (name "Net-(R46-Pad1)") (class "Default")
      (node (ref "R46") (pin "1") (pinfunction "1_1") (pintype "passive"))
      (node (ref "VT23") (pin "C") (pinfunction "C_C") (pintype "passive"))
    )
    (net (code "54") (name "Net-(R47-Pad2)") (class "Default")
      (node (ref "R47") (pin "2") (pinfunction "2_2") (pintype "passive"))
      (node (ref "VD24") (pin "C") (pinfunction "C_C") (pintype "passive"))
      (node (ref "VT24") (pin "B") (pinfunction "B_B") (pintype "passive"))
    )
    (net (code "55") (name "Net-(R48-Pad1)") (class "Default")
      (node (ref "R48") (pin "1") (pinfunction "1_1") (pintype "passive"))
      (node (ref "VT24") (pin "C") (pinfunction "C_C") (pintype "passive"))
    )
    (net (code "56") (name "Net-(R49-Pad2)") (class "Default")
      (node (ref "R49") (pin "2") (pinfunction "2_2") (pintype "passive"))
      (node (ref "VD25") (pin "C") (pinfunction "C_C") (pintype "passive"))
      (node (ref "VT25") (pin "B") (pinfunction "B_B") (pintype "passive"))
    )
    (net (code "57") (name "Net-(R50-Pad1)") (class "Default")
      (node (ref "R50") (pin "1") (pinfunction "1_1") (pintype "passive"))
      (node (ref "VT25") (pin "C") (pinfunction "C_C") (pintype "passive"))
    )
    (net (code "58") (name "Net-(R51-Pad2)") (class "Default")
      (node (ref "R51") (pin "2") (pinfunction "2_2") (pintype "passive"))
      (node (ref "VD26") (pin "C") (pinfunction "C_C") (pintype "passive"))
      (node (ref "VT26") (pin "B") (pinfunction "B_B") (pintype "passive"))
    )
    (net (code "59") (name "Net-(R52-Pad1)") (class "Default")
      (node (ref "R52") (pin "1") (pinfunction "1_1") (pintype "passive"))
      (node (ref "VT26") (pin "C") (pinfunction "C_C") (pintype "passive"))
    )
    (net (code "60") (name "Net-(R105-Pad2)") (class "Default")
      (node (ref "R105") (pin "2") (pinfunction "2_2") (pintype "passive"))
      (node (ref "VD54") (pin "C") (pinfunction "C_C") (pintype "passive"))
      (node (ref "VT54") (pin "B") (pinfunction "B_B") (pintype "passive"))
    )
    (net (code "61") (name "Net-(R111-Pad2)") (class "Default")
      (node (ref "R111") (pin "2") (pinfunction "2_2") (pintype "passive"))
      (node (ref "VD53") (pin "C") (pinfunction "C_C") (pintype "passive"))
      (node (ref "VT53") (pin "B") (pinfunction "B_B") (pintype "passive"))
    )
    (net (code "62") (name "Net-(R112-Pad1)") (class "Default")
      (node (ref "R112") (pin "1") (pinfunction "1_1") (pintype "passive"))
      (node (ref "VT53") (pin "C") (pinfunction "C_C") (pintype "passive"))
    )
    (net (code "63") (name "Net-(R114-Pad1)") (class "Default")
      (node (ref "R114") (pin "1") (pinfunction "1_1") (pintype "passive"))
      (node (ref "VT54") (pin "C") (pinfunction "C_C") (pintype "passive"))
    )
    (net (code "64") (name "R1") (class "Default")
      (node (ref "DDD1") (pin "15") (pinfunction "QA_15") (pintype "tri_state"))
      (node (ref "DDD2") (pin "5") (pinfunction "QF_5") (pintype "tri_state"))
      (node (ref "DDD4") (pin "2") (pinfunction "QC_2") (pintype "tri_state"))
      (node (ref "DDD5") (pin "7") (pinfunction "QH_7") (pintype "tri_state"))
      (node (ref "XI2") (pin "1") (pinfunction "1_1") (pintype "passive"))
      (node (ref "XN1") (pin "1") (pinfunction "1_1") (pintype "passive"))
      (node (ref "XN2") (pin "1") (pinfunction "1_1") (pintype "passive"))
      (node (ref "XN3") (pin "1") (pinfunction "1_1") (pintype "passive"))
      (node (ref "XN4") (pin "1") (pinfunction "1_1") (pintype "passive"))
      (node (ref "XO1") (pin "1") (pinfunction "1_1") (pintype "passive"))
      (node (ref "XO2A") (pin "1") (pinfunction "1_1") (pintype "passive"))
      (node (ref "XO3") (pin "1") (pinfunction "1_1") (pintype "passive"))
    )
    (net (code "65") (name "R2") (class "Default")
      (node (ref "DDD1") (pin "1") (pinfunction "QB_1") (pintype "tri_state"))
      (node (ref "DDD2") (pin "6") (pinfunction "QG_6") (pintype "tri_state"))
      (node (ref "DDD4") (pin "3") (pinfunction "QD_3") (pintype "tri_state"))
      (node (ref "DDD6") (pin "15") (pinfunction "QA_15") (pintype "tri_state"))
      (node (ref "XI2") (pin "2") (pinfunction "2_2") (pintype "passive"))
      (node (ref "XN1") (pin "2") (pinfunction "2_2") (pintype "passive"))
      (node (ref "XN2") (pin "2") (pinfunction "2_2") (pintype "passive"))
      (node (ref "XN3") (pin "2") (pinfunction "2_2") (pintype "passive"))
      (node (ref "XN4") (pin "2") (pinfunction "2_2") (pintype "passive"))
      (node (ref "XO1") (pin "2") (pinfunction "2_2") (pintype "passive"))
      (node (ref "XO2A") (pin "2") (pinfunction "2_2") (pintype "passive"))
    )
    (net (code "66") (name "R3") (class "Default")
      (node (ref "DDD1") (pin "2") (pinfunction "QC_2") (pintype "tri_state"))
      (node (ref "DDD2") (pin "7") (pinfunction "QH_7") (pintype "tri_state"))
      (node (ref "DDD4") (pin "4") (pinfunction "QE_4") (pintype "tri_state"))
      (node (ref "DDD6") (pin "1") (pinfunction "QB_1") (pintype "tri_state"))
      (node (ref "XI2") (pin "3") (pinfunction "3_3") (pintype "passive"))
      (node (ref "XN1") (pin "3") (pinfunction "3_3") (pintype "passive"))
      (node (ref "XN2") (pin "3") (pinfunction "3_3") (pintype "passive"))
      (node (ref "XN3") (pin "3") (pinfunction "3_3") (pintype "passive"))
      (node (ref "XN4") (pin "3") (pinfunction "3_3") (pintype "passive"))
      (node (ref "XO1") (pin "3") (pinfunction "3_3") (pintype "passive"))
      (node (ref "XO2A") (pin "3") (pinfunction "3_3") (pintype "passive"))
    )
    (net (code "67") (name "R4") (class "Default")
      (node (ref "DDD1") (pin "3") (pinfunction "QD_3") (pintype "tri_state"))
      (node (ref "DDD3") (pin "15") (pinfunction "QA_15") (pintype "tri_state"))
      (node (ref "DDD4") (pin "5") (pinfunction "QF_5") (pintype "tri_state"))
      (node (ref "DDD6") (pin "2") (pinfunction "QC_2") (pintype "tri_state"))
      (node (ref "XN1") (pin "4") (pinfunction "4_4") (pintype "passive"))
      (node (ref "XN2") (pin "4") (pinfunction "4_4") (pintype "passive"))
      (node (ref "XN3") (pin "4") (pinfunction "4_4") (pintype "passive"))
      (node (ref "XN4") (pin "4") (pinfunction "4_4") (pintype "passive"))
      (node (ref "XO2A") (pin "4") (pinfunction "4_4") (pintype "passive"))
    )
    (net (code "68") (name "R5") (class "Default")
      (node (ref "DDD1") (pin "4") (pinfunction "QE_4") (pintype "tri_state"))
      (node (ref "DDD3") (pin "1") (pinfunction "QB_1") (pintype "tri_state"))
      (node (ref "DDD4") (pin "6") (pinfunction "QG_6") (pintype "tri_state"))
      (node (ref "DDD6") (pin "3") (pinfunction "QD_3") (pintype "tri_state"))
      (node (ref "XN1") (pin "5") (pinfunction "5_5") (pintype "passive"))
      (node (ref "XN2") (pin "5") (pinfunction "5_5") (pintype "passive"))
      (node (ref "XN3") (pin "5") (pinfunction "5_5") (pintype "passive"))
      (node (ref "XN4") (pin "5") (pinfunction "5_5") (pintype "passive"))
      (node (ref "XO2A") (pin "5") (pinfunction "5_5") (pintype "passive"))
    )
    (net (code "69") (name "R6") (class "Default")
      (node (ref "DDD1") (pin "5") (pinfunction "QF_5") (pintype "tri_state"))
      (node (ref "DDD3") (pin "2") (pinfunction "QC_2") (pintype "tri_state"))
      (node (ref "DDD4") (pin "7") (pinfunction "QH_7") (pintype "tri_state"))
      (node (ref "DDD6") (pin "4") (pinfunction "QE_4") (pintype "tri_state"))
      (node (ref "XN1") (pin "6") (pinfunction "6_6") (pintype "passive"))
      (node (ref "XN2") (pin "6") (pinfunction "6_6") (pintype "passive"))
      (node (ref "XN3") (pin "6") (pinfunction "6_6") (pintype "passive"))
      (node (ref "XN4") (pin "6") (pinfunction "6_6") (pintype "passive"))
      (node (ref "XO2A") (pin "6") (pinfunction "6_6") (pintype "passive"))
    )
    (net (code "70") (name "R7") (class "Default")
      (node (ref "DDD1") (pin "6") (pinfunction "QG_6") (pintype "tri_state"))
      (node (ref "DDD3") (pin "3") (pinfunction "QD_3") (pintype "tri_state"))
      (node (ref "DDD5") (pin "15") (pinfunction "QA_15") (pintype "tri_state"))
      (node (ref "DDD6") (pin "5") (pinfunction "QF_5") (pintype "tri_state"))
      (node (ref "XN1") (pin "7") (pinfunction "7_7") (pintype "passive"))
      (node (ref "XN2") (pin "7") (pinfunction "7_7") (pintype "passive"))
      (node (ref "XN3") (pin "7") (pinfunction "7_7") (pintype "passive"))
      (node (ref "XN4") (pin "7") (pinfunction "7_7") (pintype "passive"))
    )
    (net (code "71") (name "R8") (class "Default")
      (node (ref "DDD1") (pin "7") (pinfunction "QH_7") (pintype "tri_state"))
      (node (ref "DDD3") (pin "4") (pinfunction "QE_4") (pintype "tri_state"))
      (node (ref "DDD5") (pin "1") (pinfunction "QB_1") (pintype "tri_state"))
      (node (ref "DDD6") (pin "6") (pinfunction "QG_6") (pintype "tri_state"))
      (node (ref "XN1") (pin "8") (pinfunction "8_8") (pintype "passive"))
      (node (ref "XN2") (pin "8") (pinfunction "8_8") (pintype "passive"))
      (node (ref "XN3") (pin "8") (pinfunction "8_8") (pintype "passive"))
      (node (ref "XN4") (pin "8") (pinfunction "8_8") (pintype "passive"))
    )
    (net (code "72") (name "R9") (class "Default")
      (node (ref "DDD2") (pin "15") (pinfunction "QA_15") (pintype "tri_state"))
      (node (ref "DDD3") (pin "5") (pinfunction "QF_5") (pintype "tri_state"))
      (node (ref "DDD5") (pin "2") (pinfunction "QC_2") (pintype "tri_state"))
      (node (ref "DDD6") (pin "7") (pinfunction "QH_7") (pintype "tri_state"))
      (node (ref "XN1") (pin "9") (pinfunction "9_9") (pintype "passive"))
      (node (ref "XN2") (pin "9") (pinfunction "9_9") (pintype "passive"))
      (node (ref "XN3") (pin "9") (pinfunction "9_9") (pintype "passive"))
      (node (ref "XN4") (pin "9") (pinfunction "9_9") (pintype "passive"))
    )
    (net (code "73") (name "R10") (class "Default")
      (node (ref "DDD2") (pin "1") (pinfunction "QB_1") (pintype "tri_state"))
      (node (ref "DDD3") (pin "6") (pinfunction "QG_6") (pintype "tri_state"))
      (node (ref "DDD5") (pin "3") (pinfunction "QD_3") (pintype "tri_state"))
      (node (ref "DDD7") (pin "15") (pinfunction "QA_15") (pintype "tri_state"))
      (node (ref "XN1") (pin "10") (pinfunction "10_10") (pintype "passive"))
      (node (ref "XN2") (pin "10") (pinfunction "10_10") (pintype "passive"))
      (node (ref "XN3") (pin "10") (pinfunction "10_10") (pintype "passive"))
      (node (ref "XN4") (pin "10") (pinfunction "10_10") (pintype "passive"))
    )
    (net (code "74") (name "R11") (class "Default")
      (node (ref "DDD2") (pin "2") (pinfunction "QC_2") (pintype "tri_state"))
      (node (ref "DDD3") (pin "7") (pinfunction "QH_7") (pintype "tri_state"))
      (node (ref "DDD5") (pin "4") (pinfunction "QE_4") (pintype "tri_state"))
      (node (ref "DDD7") (pin "1") (pinfunction "QB_1") (pintype "tri_state"))
      (node (ref "XN1") (pin "11") (pinfunction "11_11") (pintype "passive"))
      (node (ref "XN2") (pin "11") (pinfunction "11_11") (pintype "passive"))
      (node (ref "XN3") (pin "11") (pinfunction "11_11") (pintype "passive"))
      (node (ref "XN4") (pin "11") (pinfunction "11_11") (pintype "passive"))
    )
    (net (code "75") (name "R12") (class "Default")
      (node (ref "DDD2") (pin "3") (pinfunction "QD_3") (pintype "tri_state"))
      (node (ref "DDD4") (pin "15") (pinfunction "QA_15") (pintype "tri_state"))
      (node (ref "DDD5") (pin "5") (pinfunction "QF_5") (pintype "tri_state"))
      (node (ref "DDD7") (pin "2") (pinfunction "QC_2") (pintype "tri_state"))
      (node (ref "XI2B") (pin "1") (pinfunction "1_1") (pintype "passive"))
      (node (ref "XN1") (pin "12") (pinfunction "12_12") (pintype "passive"))
      (node (ref "XN2") (pin "12") (pinfunction "12_12") (pintype "passive"))
      (node (ref "XN3") (pin "12") (pinfunction "12_12") (pintype "passive"))
      (node (ref "XN4") (pin "12") (pinfunction "12_12") (pintype "passive"))
      (node (ref "XO2B") (pin "1") (pinfunction "1_1") (pintype "passive"))
    )
    (net (code "76") (name "R13") (class "Default")
      (node (ref "DDD2") (pin "4") (pinfunction "QE_4") (pintype "tri_state"))
      (node (ref "DDD4") (pin "1") (pinfunction "QB_1") (pintype "tri_state"))
      (node (ref "DDD5") (pin "6") (pinfunction "QG_6") (pintype "tri_state"))
      (node (ref "DDD7") (pin "3") (pinfunction "QD_3") (pintype "tri_state"))
      (node (ref "XI2B") (pin "2") (pinfunction "2_2") (pintype "passive"))
      (node (ref "XN1") (pin "13") (pinfunction "13_13") (pintype "passive"))
      (node (ref "XN2") (pin "13") (pinfunction "13_13") (pintype "passive"))
      (node (ref "XN3") (pin "13") (pinfunction "13_13") (pintype "passive"))
      (node (ref "XN4") (pin "13") (pinfunction "13_13") (pintype "passive"))
      (node (ref "XO2B") (pin "2") (pinfunction "2_2") (pintype "passive"))
    )
    (net (code "77") (name "RB1") (class "Default")
      (node (ref "R27") (pin "1") (pinfunction "1_1") (pintype "passive"))
    )
    (net (code "78") (name "RB2") (class "Default")
      (node (ref "R29") (pin "1") (pinfunction "1_1") (pintype "passive"))
    )
    (net (code "79") (name "RB3") (class "Default")
      (node (ref "R31") (pin "1") (pinfunction "1_1") (pintype "passive"))
    )
    (net (code "80") (name "RB4") (class "Default")
      (node (ref "R33") (pin "1") (pinfunction "1_1") (pintype "passive"))
    )
    (net (code "81") (name "RB5") (class "Default")
      (node (ref "R35") (pin "1") (pinfunction "1_1") (pintype "passive"))
    )
    (net (code "82") (name "RB6") (class "Default")
      (node (ref "R37") (pin "1") (pinfunction "1_1") (pintype "passive"))
    )
    (net (code "83") (name "RB7") (class "Default")
      (node (ref "R39") (pin "1") (pinfunction "1_1") (pintype "passive"))
    )
    (net (code "84") (name "RB8") (class "Default")
      (node (ref "R41") (pin "1") (pinfunction "1_1") (pintype "passive"))
    )
    (net (code "85") (name "RB9") (class "Default")
      (node (ref "R43") (pin "1") (pinfunction "1_1") (pintype "passive"))
    )
    (net (code "86") (name "RB10") (class "Default")
      (node (ref "R45") (pin "1") (pinfunction "1_1") (pintype "passive"))
    )
    (net (code "87") (name "RB11") (class "Default")
      (node (ref "R47") (pin "1") (pinfunction "1_1") (pintype "passive"))
    )
    (net (code "88") (name "RB12") (class "Default")
      (node (ref "R49") (pin "1") (pinfunction "1_1") (pintype "passive"))
    )
    (net (code "89") (name "RB13") (class "Default")
      (node (ref "R51") (pin "1") (pinfunction "1_1") (pintype "passive"))
    )
    (net (code "90") (name "RCLOCK") (class "Default")
      (node (ref "DDD1") (pin "11") (pinfunction "SCK_11") (pintype "input"))
      (node (ref "DDD2") (pin "11") (pinfunction "SCK_11") (pintype "input"))
      (node (ref "DDD3") (pin "11") (pinfunction "SCK_11") (pintype "input"))
      (node (ref "DDD4") (pin "11") (pinfunction "SCK_11") (pintype "input"))
      (node (ref "DDD5") (pin "11") (pinfunction "SCK_11") (pintype "input"))
      (node (ref "DDD6") (pin "11") (pinfunction "SCK_11") (pintype "input"))
      (node (ref "DDD7") (pin "11") (pinfunction "SCK_11") (pintype "input"))
      (node (ref "JP2") (pin "3") (pinfunction "3_3") (pintype "passive"))
    )
    (net (code "91") (name "RCLOCK_MISO_D12") (class "Default")
      (node (ref "DD2") (pin "16") (pinfunction "PB4(MISO)_16") (pintype "bidirectional"))
      (node (ref "ISP") (pin "1") (pinfunction "1_1") (pintype "passive"))
    )
    (net (code "92") (name "RDATA") (class "Default")
      (node (ref "DDD5") (pin "14") (pinfunction "SER_14") (pintype "input"))
    )
    (net (code "93") (name "RDATA_MOSI_D11") (class "Default")
      (node (ref "DD2") (pin "15") (pinfunction "PB3(MOSI/OC2)_15") (pintype "bidirectional"))
      (node (ref "ISP") (pin "4") (pinfunction "4_4") (pintype "passive"))
    )
    (net (code "94") (name "RE1") (class "Default")
      (node (ref "R111") (pin "1") (pinfunction "1_1") (pintype "passive"))
      (node (ref "RE1") (pin "1") (pinfunction "1_1") (pintype "passive"))
    )
    (net (code "95") (name "RE2") (class "Default")
      (node (ref "R105") (pin "1") (pinfunction "1_1") (pintype "passive"))
      (node (ref "RE2") (pin "1") (pinfunction "1_1") (pintype "passive"))
    )
    (net (code "96") (name "RESET") (class "Default")
      (node (ref "DD2") (pin "29") (pinfunction "PC6(/RESET)_29") (pintype "bidirectional"))
      (node (ref "ISP") (pin "5") (pinfunction "5_5") (pintype "passive"))
      (node (ref "R109") (pin "1") (pinfunction "1_1") (pintype "passive"))
    )
    (net (code "97") (name "RLATCH") (class "Default")
      (node (ref "DDD1") (pin "12") (pinfunction "RCK_12") (pintype "input"))
      (node (ref "DDD2") (pin "12") (pinfunction "RCK_12") (pintype "input"))
      (node (ref "DDD3") (pin "12") (pinfunction "RCK_12") (pintype "input"))
      (node (ref "DDD4") (pin "12") (pinfunction "RCK_12") (pintype "input"))
      (node (ref "DDD5") (pin "12") (pinfunction "RCK_12") (pintype "input"))
      (node (ref "DDD6") (pin "12") (pinfunction "RCK_12") (pintype "input"))
      (node (ref "DDD7") (pin "12") (pinfunction "RCK_12") (pintype "input"))
      (node (ref "JP2") (pin "2") (pinfunction "2_2") (pintype "passive"))
    )
    (net (code "98") (name "RLATCH_D10") (class "Default")
      (node (ref "DD2") (pin "14") (pinfunction "PB2(SS/OC1B)_14") (pintype "bidirectional"))
    )
    (net (code "99") (name "SCK") (class "Default")
      (node (ref "DD2") (pin "17") (pinfunction "PB5(SCK)_17") (pintype "bidirectional"))
      (node (ref "ISP") (pin "3") (pinfunction "3_3") (pintype "passive"))
    )
    (net (code "100") (name "SCL") (class "Default")
      (node (ref "DD1B") (pin "6") (pinfunction "SCL_6") (pintype "input"))
      (node (ref "DD2") (pin "28") (pinfunction "PC5(ADC5/SCL)_28") (pintype "bidirectional"))
      (node (ref "J4") (pin "2") (pinfunction "2_2") (pintype "passive"))
      (node (ref "R108") (pin "1") (pinfunction "1_1") (pintype "passive"))
    )
    (net (code "101") (name "SDA") (class "Default")
      (node (ref "DD1A") (pin "15") (pinfunction "SDA_15") (pintype "bidirectional"))
      (node (ref "DD1B") (pin "5") (pinfunction "SDA_5") (pintype "bidirectional"))
      (node (ref "DD2") (pin "27") (pinfunction "PC4(ADC4/SDA)_27") (pintype "bidirectional"))
      (node (ref "R107") (pin "1") (pinfunction "1_1") (pintype "passive"))
    )
    (net (code "102") (name "SEQ") (class "Default")
      (node (ref "DD1B") (pin "7") (pinfunction "SQW_7") (pintype "open_collector"))
      (node (ref "DD2") (pin "32") (pinfunction "PD2(INT0)_32") (pintype "bidirectional"))
      (node (ref "J5") (pin "1") (pinfunction "1_1") (pintype "passive"))
      (node (ref "R106") (pin "1") (pinfunction "1_1") (pintype "passive"))
    )
    (net (code "103") (name "SER0") (class "Default")
      (node (ref "DDD1") (pin "14") (pinfunction "SER_14") (pintype "input"))
      (node (ref "DDD3") (pin "14") (pinfunction "SER_14") (pintype "input"))
      (node (ref "DDD6") (pin "14") (pinfunction "SER_14") (pintype "input"))
      (node (ref "JP2") (pin "1") (pinfunction "1_1") (pintype "passive"))
    )
    (net (code "104") (name "SER1") (class "Default")
      (node (ref "DDD1") (pin "9") (pinfunction "QH*_9") (pintype "tri_state"))
      (node (ref "DDD2") (pin "14") (pinfunction "SER_14") (pintype "input"))
      (node (ref "DDD3") (pin "9") (pinfunction "QH*_9") (pintype "tri_state"))
      (node (ref "DDD4") (pin "14") (pinfunction "SER_14") (pintype "input"))
      (node (ref "DDD6") (pin "9") (pinfunction "QH*_9") (pintype "tri_state"))
      (node (ref "DDD7") (pin "14") (pinfunction "SER_14") (pintype "input"))
      (node (ref "JP2") (pin "4") (pinfunction "4_4") (pintype "passive"))
    )
    (net (code "105") (name "SER2") (class "Default")
      (node (ref "DDD2") (pin "9") (pinfunction "QH*_9") (pintype "tri_state"))
      (node (ref "DDD4") (pin "9") (pinfunction "QH*_9") (pintype "tri_state"))
      (node (ref "DDD5") (pin "9") (pinfunction "QH*_9") (pintype "tri_state"))
      (node (ref "DDD7") (pin "9") (pinfunction "QH*_9") (pintype "tri_state"))
      (node (ref "JP2") (pin "5") (pinfunction "5_5") (pintype "passive"))
    )
    (net (code "106") (name "VBAT") (class "Default")
      (node (ref "BT1") (pin "1") (pinfunction "+_1") (pintype "power_in"))
      (node (ref "C8") (pin "1") (pinfunction "1_1") (pintype "passive"))
      (node (ref "DD1A") (pin "14") (pinfunction "VBAT_14") (pintype "bidirectional"))
      (node (ref "DD1B") (pin "3") (pinfunction "VBAT_3") (pintype "passive"))
    )
    (net (code "107") (name "VCC") (class "Default")
      (node (ref "DD1B1") (pin "8") (pinfunction "VCC_8") (pintype "power_in"))
    )
    (net (code "108") (name "unconnected-(DD1B1-SCL-Pad6)") (class "Default")
      (node (ref "DD1B1") (pin "6") (pinfunction "SCL_6") (pintype "input"))
    )
    (net (code "109") (name "unconnected-(DD1B1-SDA-Pad5)") (class "Default")
      (node (ref "DD1B1") (pin "5") (pinfunction "SDA_5") (pintype "bidirectional"))
    )
    (net (code "110") (name "unconnected-(DD1B1-SQW-Pad7)") (class "Default")
      (node (ref "DD1B1") (pin "7") (pinfunction "SQW_7") (pintype "open_collector"))
    )
    (net (code "111") (name "unconnected-(DD1B1-VBAT-Pad3)") (class "Default")
      (node (ref "DD1B1") (pin "3") (pinfunction "VBAT_3") (pintype "passive"))
    )
    (net (code "112") (name "unconnected-(DD1B1-X1-Pad1)") (class "Default")
      (node (ref "DD1B1") (pin "1") (pinfunction "X1_1") (pintype "input"))
    )
    (net (code "113") (name "unconnected-(DD1B1-X2-Pad2)") (class "Default")
      (node (ref "DD1B1") (pin "2") (pinfunction "X2_2") (pintype "output"))
    )
    (net (code "114") (name "unconnected-(DD2-ADC6-Pad19)") (class "Default")
      (node (ref "DD2") (pin "19") (pinfunction "ADC6_19") (pintype "bidirectional"))
    )
    (net (code "115") (name "unconnected-(DD2-ADC7-Pad22)") (class "Default")
      (node (ref "DD2") (pin "22") (pinfunction "ADC7_22") (pintype "bidirectional"))
    )
    (net (code "116") (name "unconnected-(DD2-AREF-Pad20)") (class "Default")
      (node (ref "DD2") (pin "20") (pinfunction "AREF_20") (pintype "passive"))
    )
    (net (code "117") (name "unconnected-(DD2-PB0(ICP)-Pad12)") (class "Default")
      (node (ref "DD2") (pin "12") (pinfunction "PB0(ICP)_12") (pintype "bidirectional"))
    )
    (net (code "118") (name "unconnected-(DD2-PB1(OC1A)-Pad13)") (class "Default")
      (node (ref "DD2") (pin "13") (pinfunction "PB1(OC1A)_13") (pintype "bidirectional"))
    )
    (net (code "119") (name "unconnected-(DD2-PC0(ADC0)-Pad23)") (class "Default")
      (node (ref "DD2") (pin "23") (pinfunction "PC0(ADC0)_23") (pintype "bidirectional"))
    )
    (net (code "120") (name "unconnected-(DD2-PC1(ADC1)-Pad24)") (class "Default")
      (node (ref "DD2") (pin "24") (pinfunction "PC1(ADC1)_24") (pintype "bidirectional"))
    )
    (net (code "121") (name "unconnected-(DD2-PC2(ADC2)-Pad25)") (class "Default")
      (node (ref "DD2") (pin "25") (pinfunction "PC2(ADC2)_25") (pintype "bidirectional"))
    )
    (net (code "122") (name "unconnected-(DD2-PC3(ADC3)-Pad26)") (class "Default")
      (node (ref "DD2") (pin "26") (pinfunction "PC3(ADC3)_26") (pintype "bidirectional"))
    )
    (net (code "123") (name "unconnected-(DD2-PD0(RXD)-Pad30)") (class "Default")
      (node (ref "DD2") (pin "30") (pinfunction "PD0(RXD)_30") (pintype "bidirectional"))
    )
    (net (code "124") (name "unconnected-(DD2-PD1(TXD)-Pad31)") (class "Default")
      (node (ref "DD2") (pin "31") (pinfunction "PD1(TXD)_31") (pintype "bidirectional"))
    )
    (net (code "125") (name "unconnected-(DD2-PD3(INT1)-Pad1)") (class "Default")
      (node (ref "DD2") (pin "1") (pinfunction "PD3(INT1)_1") (pintype "bidirectional"))
    )
    (net (code "126") (name "unconnected-(DD2-PD4(XCK{slash}T0)-Pad2)") (class "Default")
      (node (ref "DD2") (pin "2") (pinfunction "PD4(XCK/T0)_2") (pintype "bidirectional"))
    )
    (net (code "127") (name "unconnected-(DD2-PD5(T1)-Pad9)") (class "Default")
      (node (ref "DD2") (pin "9") (pinfunction "PD5(T1)_9") (pintype "bidirectional"))
    )
    (net (code "128") (name "unconnected-(DD2-PD6(AIN0)-Pad10)") (class "Default")
      (node (ref "DD2") (pin "10") (pinfunction "PD6(AIN0)_10") (pintype "bidirectional"))
    )
    (net (code "129") (name "unconnected-(DD2-PD7(AIN1)-Pad11)") (class "Default")
      (node (ref "DD2") (pin "11") (pinfunction "PD7(AIN1)_11") (pintype "bidirectional"))
    )
    (net (code "130") (name "unconnected-(JS1-Pad1)") (class "Default")
      (node (ref "JS1") (pin "1") (pinfunction "1_1") (pintype "passive"))
    )
    (net (code "131") (name "unconnected-(JS1-Pad2)") (class "Default")
      (node (ref "JS1") (pin "2") (pinfunction "2_2") (pintype "passive"))
    )
    (net (code "132") (name "unconnected-(JS1-Pad3)") (class "Default")
      (node (ref "JS1") (pin "3") (pinfunction "3_3") (pintype "passive"))
    )
    (net (code "133") (name "unconnected-(R52-Pad2)") (class "Default")
      (node (ref "R52") (pin "2") (pinfunction "2_2") (pintype "passive"))
    )
  )
)
